# GS_02_Core.net
KiCad netlist of a schematic drawn in Altium Designer
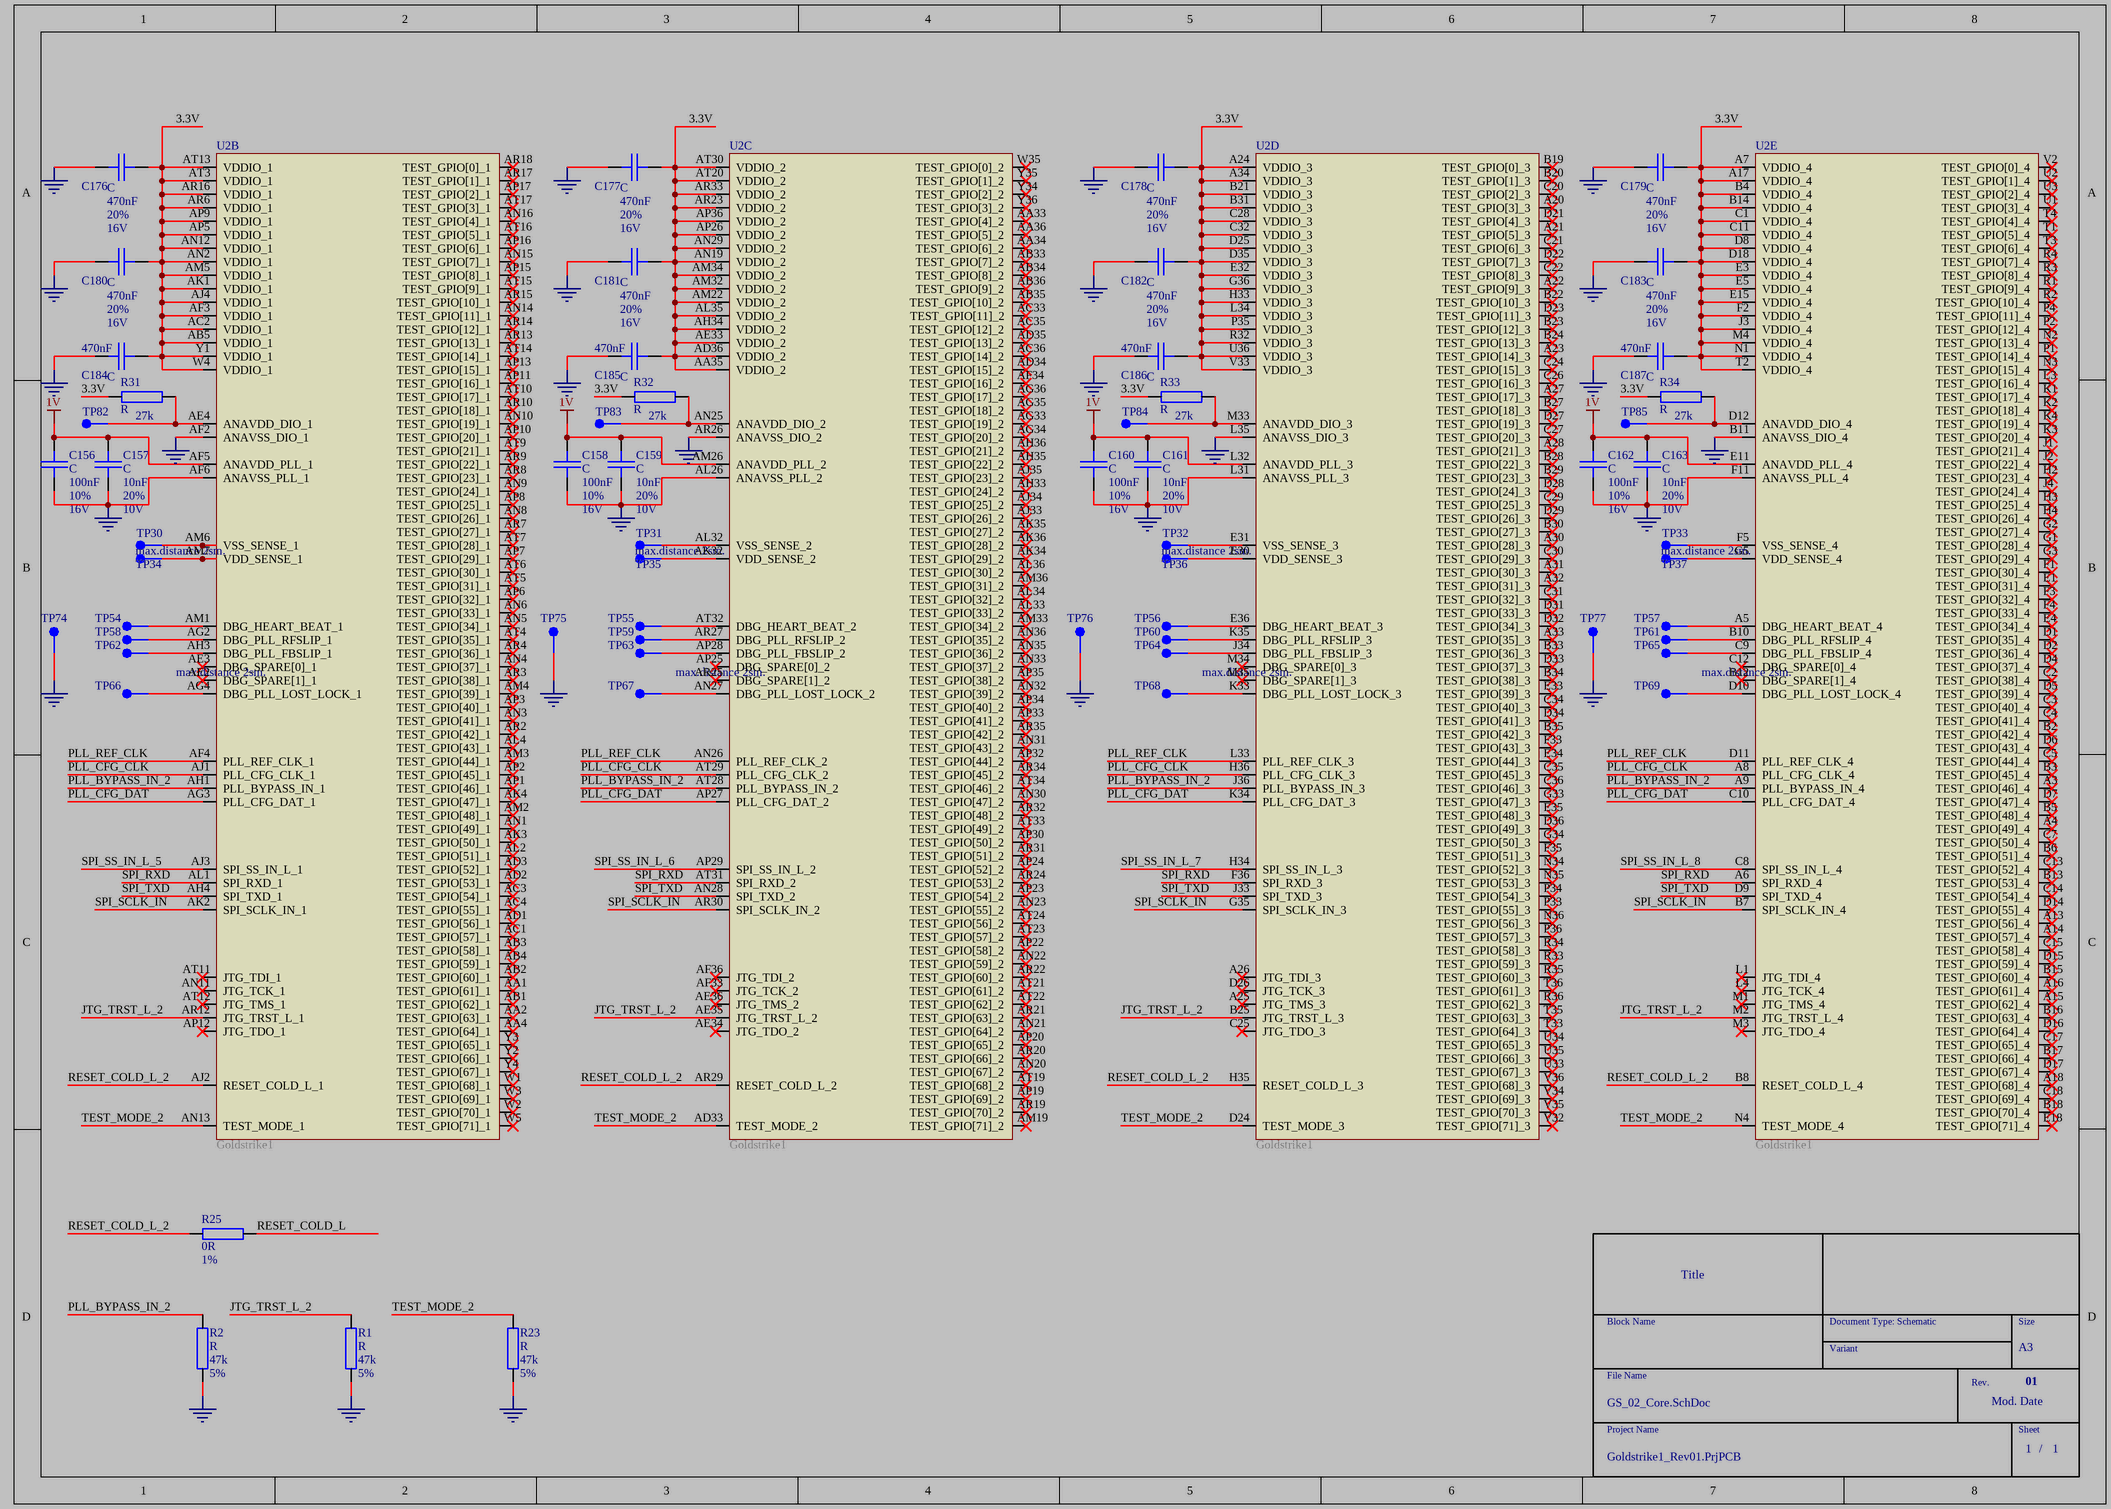
[diagram p0: GS_02_Core.SchDoc]

(export (version "E")
  (design (tool "Eeschema 10.0.6"))
  (components
    (comp (ref "C156")
      (value "C")
      (footprint "SMD_0603_CAPC1608X95N")
      (fields
        (field (name "DB_PART_NUMBER") "CAP000047357")
        (field (name "DB_VALUE") "100nF")
        (field (name "DB_TOLERANCE") "10%")
        (field (name "DB_VOLTAGE") "16V")
      )
      (libsource (lib "Database_Libs1") (part "C"))
    )
    (comp (ref "C157")
      (value "C")
      (footprint "SMD_0603_CAPC1608X95N")
      (fields
        (field (name "DB_PART_NUMBER") "CAP000038821")
        (field (name "DB_VALUE") "10nF")
        (field (name "DB_TOLERANCE") "20%")
        (field (name "DB_VOLTAGE") "10V")
      )
      (libsource (lib "Database_Libs1") (part "C"))
    )
    (comp (ref "C158")
      (value "C")
      (footprint "SMD_0603_CAPC1608X95N")
      (fields
        (field (name "DB_PART_NUMBER") "CAP000047357")
        (field (name "DB_VALUE") "100nF")
        (field (name "DB_TOLERANCE") "10%")
        (field (name "DB_VOLTAGE") "16V")
      )
      (libsource (lib "Database_Libs1") (part "C"))
    )
    (comp (ref "C159")
      (value "C")
      (footprint "SMD_0603_CAPC1608X95N")
      (fields
        (field (name "DB_PART_NUMBER") "CAP000038821")
        (field (name "DB_VALUE") "10nF")
        (field (name "DB_TOLERANCE") "20%")
        (field (name "DB_VOLTAGE") "10V")
      )
      (libsource (lib "Database_Libs1") (part "C"))
    )
    (comp (ref "C160")
      (value "C")
      (footprint "SMD_0603_CAPC1608X95N")
      (fields
        (field (name "DB_PART_NUMBER") "CAP000047357")
        (field (name "DB_VALUE") "100nF")
        (field (name "DB_TOLERANCE") "10%")
        (field (name "DB_VOLTAGE") "16V")
      )
      (libsource (lib "Database_Libs1") (part "C"))
    )
    (comp (ref "C161")
      (value "C")
      (footprint "SMD_0603_CAPC1608X95N")
      (fields
        (field (name "DB_PART_NUMBER") "CAP000038821")
        (field (name "DB_VALUE") "10nF")
        (field (name "DB_TOLERANCE") "20%")
        (field (name "DB_VOLTAGE") "10V")
      )
      (libsource (lib "Database_Libs1") (part "C"))
    )
    (comp (ref "C162")
      (value "C")
      (footprint "SMD_0603_CAPC1608X95N")
      (fields
        (field (name "DB_PART_NUMBER") "CAP000047357")
        (field (name "DB_VALUE") "100nF")
        (field (name "DB_TOLERANCE") "10%")
        (field (name "DB_VOLTAGE") "16V")
      )
      (libsource (lib "Database_Libs1") (part "C"))
    )
    (comp (ref "C163")
      (value "C")
      (footprint "SMD_0603_CAPC1608X95N")
      (fields
        (field (name "DB_PART_NUMBER") "CAP000038821")
        (field (name "DB_VALUE") "10nF")
        (field (name "DB_TOLERANCE") "20%")
        (field (name "DB_VOLTAGE") "10V")
      )
      (libsource (lib "Database_Libs1") (part "C"))
    )
    (comp (ref "C176")
      (value "C")
      (footprint "SMD_0603_CAPC1608X95N")
      (fields
        (field (name "DB_PART_NUMBER") "CAP000023179")
        (field (name "DB_VALUE") "470nF")
        (field (name "DB_TOLERANCE") "20%")
        (field (name "DB_VOLTAGE") "16V")
        (field (name "DB_MANUFACTURER_PART") "KEMET    C0603F474M4RAC")
      )
      (libsource (lib "Database_Libs1") (part "C"))
    )
    (comp (ref "C177")
      (value "C")
      (footprint "SMD_0603_CAPC1608X95N")
      (fields
        (field (name "DB_PART_NUMBER") "CAP000023179")
        (field (name "DB_VALUE") "470nF")
        (field (name "DB_TOLERANCE") "20%")
        (field (name "DB_VOLTAGE") "16V")
        (field (name "DB_MANUFACTURER_PART") "KEMET    C0603F474M4RAC")
      )
      (libsource (lib "Database_Libs1") (part "C"))
    )
    (comp (ref "C178")
      (value "C")
      (footprint "SMD_0603_CAPC1608X95N")
      (fields
        (field (name "DB_PART_NUMBER") "CAP000023179")
        (field (name "DB_VALUE") "470nF")
        (field (name "DB_TOLERANCE") "20%")
        (field (name "DB_VOLTAGE") "16V")
        (field (name "DB_MANUFACTURER_PART") "KEMET    C0603F474M4RAC")
      )
      (libsource (lib "Database_Libs1") (part "C"))
    )
    (comp (ref "C179")
      (value "C")
      (footprint "SMD_0603_CAPC1608X95N")
      (fields
        (field (name "DB_PART_NUMBER") "CAP000023179")
        (field (name "DB_VALUE") "470nF")
        (field (name "DB_TOLERANCE") "20%")
        (field (name "DB_VOLTAGE") "16V")
        (field (name "DB_MANUFACTURER_PART") "KEMET    C0603F474M4RAC")
      )
      (libsource (lib "Database_Libs1") (part "C"))
    )
    (comp (ref "C180")
      (value "C")
      (footprint "SMD_0603_CAPC1608X95N")
      (fields
        (field (name "DB_PART_NUMBER") "CAP000023179")
        (field (name "DB_VALUE") "470nF")
        (field (name "DB_TOLERANCE") "20%")
        (field (name "DB_VOLTAGE") "16V")
        (field (name "DB_MANUFACTURER_PART") "KEMET    C0603F474M4RAC")
      )
      (libsource (lib "Database_Libs1") (part "C"))
    )
    (comp (ref "C181")
      (value "C")
      (footprint "SMD_0603_CAPC1608X95N")
      (fields
        (field (name "DB_PART_NUMBER") "CAP000023179")
        (field (name "DB_VALUE") "470nF")
        (field (name "DB_TOLERANCE") "20%")
        (field (name "DB_VOLTAGE") "16V")
        (field (name "DB_MANUFACTURER_PART") "KEMET    C0603F474M4RAC")
      )
      (libsource (lib "Database_Libs1") (part "C"))
    )
    (comp (ref "C182")
      (value "C")
      (footprint "SMD_0603_CAPC1608X95N")
      (fields
        (field (name "DB_PART_NUMBER") "CAP000023179")
        (field (name "DB_VALUE") "470nF")
        (field (name "DB_TOLERANCE") "20%")
        (field (name "DB_VOLTAGE") "16V")
        (field (name "DB_MANUFACTURER_PART") "KEMET    C0603F474M4RAC")
      )
      (libsource (lib "Database_Libs1") (part "C"))
    )
    (comp (ref "C183")
      (value "C")
      (footprint "SMD_0603_CAPC1608X95N")
      (fields
        (field (name "DB_PART_NUMBER") "CAP000023179")
        (field (name "DB_VALUE") "470nF")
        (field (name "DB_TOLERANCE") "20%")
        (field (name "DB_VOLTAGE") "16V")
        (field (name "DB_MANUFACTURER_PART") "KEMET    C0603F474M4RAC")
      )
      (libsource (lib "Database_Libs1") (part "C"))
    )
    (comp (ref "C184")
      (value "C")
      (footprint "SMD_0603_CAPC1608X95N")
      (fields
        (field (name "DB_PART_NUMBER") "CAP000023179")
        (field (name "DB_VALUE") "470nF")
        (field (name "DB_MANUFACTURER_PART") "KEMET    C0603F474M4RAC")
      )
      (libsource (lib "Database_Libs1") (part "C"))
    )
    (comp (ref "C185")
      (value "C")
      (footprint "SMD_0603_CAPC1608X95N")
      (fields
        (field (name "DB_PART_NUMBER") "CAP000023179")
        (field (name "DB_VALUE") "470nF")
        (field (name "DB_MANUFACTURER_PART") "KEMET    C0603F474M4RAC")
      )
      (libsource (lib "Database_Libs1") (part "C"))
    )
    (comp (ref "C186")
      (value "C")
      (footprint "SMD_0603_CAPC1608X95N")
      (fields
        (field (name "DB_PART_NUMBER") "CAP000023179")
        (field (name "DB_VALUE") "470nF")
        (field (name "DB_MANUFACTURER_PART") "KEMET    C0603F474M4RAC")
      )
      (libsource (lib "Database_Libs1") (part "C"))
    )
    (comp (ref "C187")
      (value "C")
      (footprint "SMD_0603_CAPC1608X95N")
      (fields
        (field (name "DB_PART_NUMBER") "CAP000023179")
        (field (name "DB_VALUE") "470nF")
        (field (name "DB_MANUFACTURER_PART") "KEMET    C0603F474M4RAC")
      )
      (libsource (lib "Database_Libs1") (part "C"))
    )
    (comp (ref "R1")
      (value "R")
      (footprint "SMD_0603_RESC1608X55N")
      (fields
        (field (name "DB_PART_NUMBER") "RES000006462")
        (field (name "DB_VALUE") "47k")
        (field (name "DB_TOLERANCE") "5%")
        (field (name "DB_MANUFACTURER_PART") "YAGEO    RC0603JR-0747K")
      )
      (libsource (lib "Database_Libs1") (part "R"))
    )
    (comp (ref "R2")
      (value "R")
      (footprint "SMD_0603_RESC1608X55N")
      (fields
        (field (name "DB_PART_NUMBER") "RES000006462")
        (field (name "DB_VALUE") "47k")
        (field (name "DB_TOLERANCE") "5%")
        (field (name "DB_MANUFACTURER_PART") "YAGEO    RC0603JR-0747K")
      )
      (libsource (lib "Database_Libs1") (part "R"))
    )
    (comp (ref "R23")
      (value "R")
      (footprint "SMD_0603_RESC1608X55N")
      (fields
        (field (name "DB_PART_NUMBER") "RES000006462")
        (field (name "DB_VALUE") "47k")
        (field (name "DB_TOLERANCE") "5%")
        (field (name "DB_MANUFACTURER_PART") "YAGEO    RC0603JR-0747K")
      )
      (libsource (lib "Database_Libs1") (part "R"))
    )
    (comp (ref "R25")
      (value "R")
      (footprint "SMD_0603_RESC1608X55N")
      (fields
        (field (name "DB_PART_NUMBER") "RES000008926")
        (field (name "DB_VALUE") "0R")
        (field (name "DB_TOLERANCE") "1%")
        (field (name "DB_MANUFACTURER_PART") "YAGEO    AC0603FR-070RL")
        (field (name "DB_APPROVED_BY") "VSN")
      )
      (libsource (lib "Database_Libs1") (part "R"))
    )
    (comp (ref "R31")
      (value "R")
      (footprint "SMD_0603_RESC1608X55N")
      (fields
        (field (name "DB_PART_NUMBER") "RES000006456")
        (field (name "DB_VALUE") "27k")
        (field (name "DB_MANUFACTURER_PART") "YAGEO    RC0603JR-0727K")
      )
      (libsource (lib "Database_Libs1") (part "R"))
    )
    (comp (ref "R32")
      (value "R")
      (footprint "SMD_0603_RESC1608X55N")
      (fields
        (field (name "DB_PART_NUMBER") "RES000006456")
        (field (name "DB_VALUE") "27k")
        (field (name "DB_MANUFACTURER_PART") "YAGEO    RC0603JR-0727K")
      )
      (libsource (lib "Database_Libs1") (part "R"))
    )
    (comp (ref "R33")
      (value "R")
      (footprint "SMD_0603_RESC1608X55N")
      (fields
        (field (name "DB_PART_NUMBER") "RES000006456")
        (field (name "DB_VALUE") "27k")
        (field (name "DB_MANUFACTURER_PART") "YAGEO    RC0603JR-0727K")
      )
      (libsource (lib "Database_Libs1") (part "R"))
    )
    (comp (ref "R34")
      (value "R")
      (footprint "SMD_0603_RESC1608X55N")
      (fields
        (field (name "DB_PART_NUMBER") "RES000006456")
        (field (name "DB_VALUE") "27k")
        (field (name "DB_MANUFACTURER_PART") "YAGEO    RC0603JR-0727K")
      )
      (libsource (lib "Database_Libs1") (part "R"))
    )
    (comp (ref "TP30")
      (value "TEST_POINT_1")
      (footprint "SMD_TP_100-254")
      (fields (field (name "DB_PART_NUMBER") "TPO000000001"))
      (libsource (lib "Database_Libs1") (part "TEST_POINT_1"))
    )
    (comp (ref "TP31")
      (value "TEST_POINT_1")
      (footprint "SMD_TP_100-254")
      (fields (field (name "DB_PART_NUMBER") "TPO000000001"))
      (libsource (lib "Database_Libs1") (part "TEST_POINT_1"))
    )
    (comp (ref "TP32")
      (value "TEST_POINT_1")
      (footprint "SMD_TP_100-254")
      (fields (field (name "DB_PART_NUMBER") "TPO000000001"))
      (libsource (lib "Database_Libs1") (part "TEST_POINT_1"))
    )
    (comp (ref "TP33")
      (value "TEST_POINT_1")
      (footprint "SMD_TP_100-254")
      (fields (field (name "DB_PART_NUMBER") "TPO000000001"))
      (libsource (lib "Database_Libs1") (part "TEST_POINT_1"))
    )
    (comp (ref "TP34")
      (value "TEST_POINT_1")
      (footprint "SMD_TP_100-254")
      (fields (field (name "DB_PART_NUMBER") "TPO000000001"))
      (libsource (lib "Database_Libs1") (part "TEST_POINT_1"))
    )
    (comp (ref "TP35")
      (value "TEST_POINT_1")
      (footprint "SMD_TP_100-254")
      (fields (field (name "DB_PART_NUMBER") "TPO000000001"))
      (libsource (lib "Database_Libs1") (part "TEST_POINT_1"))
    )
    (comp (ref "TP36")
      (value "TEST_POINT_1")
      (footprint "SMD_TP_100-254")
      (fields (field (name "DB_PART_NUMBER") "TPO000000001"))
      (libsource (lib "Database_Libs1") (part "TEST_POINT_1"))
    )
    (comp (ref "TP37")
      (value "TEST_POINT_1")
      (footprint "SMD_TP_100-254")
      (fields (field (name "DB_PART_NUMBER") "TPO000000001"))
      (libsource (lib "Database_Libs1") (part "TEST_POINT_1"))
    )
    (comp (ref "TP54")
      (value "TEST_POINT_1")
      (footprint "SMD_TP_100-254")
      (fields (field (name "DB_PART_NUMBER") "TPO000000001"))
      (libsource (lib "Database_Libs1") (part "TEST_POINT_1"))
    )
    (comp (ref "TP55")
      (value "TEST_POINT_1")
      (footprint "SMD_TP_100-254")
      (fields (field (name "DB_PART_NUMBER") "TPO000000001"))
      (libsource (lib "Database_Libs1") (part "TEST_POINT_1"))
    )
    (comp (ref "TP56")
      (value "TEST_POINT_1")
      (footprint "SMD_TP_100-254")
      (fields (field (name "DB_PART_NUMBER") "TPO000000001"))
      (libsource (lib "Database_Libs1") (part "TEST_POINT_1"))
    )
    (comp (ref "TP57")
      (value "TEST_POINT_1")
      (footprint "SMD_TP_100-254")
      (fields (field (name "DB_PART_NUMBER") "TPO000000001"))
      (libsource (lib "Database_Libs1") (part "TEST_POINT_1"))
    )
    (comp (ref "TP58")
      (value "TEST_POINT_1")
      (footprint "SMD_TP_100-254")
      (fields (field (name "DB_PART_NUMBER") "TPO000000001"))
      (libsource (lib "Database_Libs1") (part "TEST_POINT_1"))
    )
    (comp (ref "TP59")
      (value "TEST_POINT_1")
      (footprint "SMD_TP_100-254")
      (fields (field (name "DB_PART_NUMBER") "TPO000000001"))
      (libsource (lib "Database_Libs1") (part "TEST_POINT_1"))
    )
    (comp (ref "TP60")
      (value "TEST_POINT_1")
      (footprint "SMD_TP_100-254")
      (fields (field (name "DB_PART_NUMBER") "TPO000000001"))
      (libsource (lib "Database_Libs1") (part "TEST_POINT_1"))
    )
    (comp (ref "TP61")
      (value "TEST_POINT_1")
      (footprint "SMD_TP_100-254")
      (fields (field (name "DB_PART_NUMBER") "TPO000000001"))
      (libsource (lib "Database_Libs1") (part "TEST_POINT_1"))
    )
    (comp (ref "TP62")
      (value "TEST_POINT_1")
      (footprint "SMD_TP_100-254")
      (fields (field (name "DB_PART_NUMBER") "TPO000000001"))
      (libsource (lib "Database_Libs1") (part "TEST_POINT_1"))
    )
    (comp (ref "TP63")
      (value "TEST_POINT_1")
      (footprint "SMD_TP_100-254")
      (fields (field (name "DB_PART_NUMBER") "TPO000000001"))
      (libsource (lib "Database_Libs1") (part "TEST_POINT_1"))
    )
    (comp (ref "TP64")
      (value "TEST_POINT_1")
      (footprint "SMD_TP_100-254")
      (fields (field (name "DB_PART_NUMBER") "TPO000000001"))
      (libsource (lib "Database_Libs1") (part "TEST_POINT_1"))
    )
    (comp (ref "TP65")
      (value "TEST_POINT_1")
      (footprint "SMD_TP_100-254")
      (fields (field (name "DB_PART_NUMBER") "TPO000000001"))
      (libsource (lib "Database_Libs1") (part "TEST_POINT_1"))
    )
    (comp (ref "TP66")
      (value "TEST_POINT_1")
      (footprint "SMD_TP_100-254")
      (fields (field (name "DB_PART_NUMBER") "TPO000000001"))
      (libsource (lib "Database_Libs1") (part "TEST_POINT_1"))
    )
    (comp (ref "TP67")
      (value "TEST_POINT_1")
      (footprint "SMD_TP_100-254")
      (fields (field (name "DB_PART_NUMBER") "TPO000000001"))
      (libsource (lib "Database_Libs1") (part "TEST_POINT_1"))
    )
    (comp (ref "TP68")
      (value "TEST_POINT_1")
      (footprint "SMD_TP_100-254")
      (fields (field (name "DB_PART_NUMBER") "TPO000000001"))
      (libsource (lib "Database_Libs1") (part "TEST_POINT_1"))
    )
    (comp (ref "TP69")
      (value "TEST_POINT_1")
      (footprint "SMD_TP_100-254")
      (fields (field (name "DB_PART_NUMBER") "TPO000000001"))
      (libsource (lib "Database_Libs1") (part "TEST_POINT_1"))
    )
    (comp (ref "TP74")
      (value "TEST_POINT_1")
      (footprint "SMD_TP_100-254")
      (fields (field (name "DB_PART_NUMBER") "TPO000000001"))
      (libsource (lib "Database_Libs1") (part "TEST_POINT_1"))
    )
    (comp (ref "TP75")
      (value "TEST_POINT_1")
      (footprint "SMD_TP_100-254")
      (fields (field (name "DB_PART_NUMBER") "TPO000000001"))
      (libsource (lib "Database_Libs1") (part "TEST_POINT_1"))
    )
    (comp (ref "TP76")
      (value "TEST_POINT_1")
      (footprint "SMD_TP_100-254")
      (fields (field (name "DB_PART_NUMBER") "TPO000000001"))
      (libsource (lib "Database_Libs1") (part "TEST_POINT_1"))
    )
    (comp (ref "TP77")
      (value "TEST_POINT_1")
      (footprint "SMD_TP_100-254")
      (fields (field (name "DB_PART_NUMBER") "TPO000000001"))
      (libsource (lib "Database_Libs1") (part "TEST_POINT_1"))
    )
    (comp (ref "TP82")
      (value "TEST_POINT_1")
      (footprint "SMD_TP_100-254")
      (fields (field (name "DB_PART_NUMBER") "TPO000000001"))
      (libsource (lib "Database_Libs1") (part "TEST_POINT_1"))
    )
    (comp (ref "TP83")
      (value "TEST_POINT_1")
      (footprint "SMD_TP_100-254")
      (fields (field (name "DB_PART_NUMBER") "TPO000000001"))
      (libsource (lib "Database_Libs1") (part "TEST_POINT_1"))
    )
    (comp (ref "TP84")
      (value "TEST_POINT_1")
      (footprint "SMD_TP_100-254")
      (fields (field (name "DB_PART_NUMBER") "TPO000000001"))
      (libsource (lib "Database_Libs1") (part "TEST_POINT_1"))
    )
    (comp (ref "TP85")
      (value "TEST_POINT_1")
      (footprint "SMD_TP_100-254")
      (fields (field (name "DB_PART_NUMBER") "TPO000000001"))
      (libsource (lib "Database_Libs1") (part "TEST_POINT_1"))
    )
    (comp (ref "U2") (value "Goldstrike1") (libsource (lib "Schlib1") (part "Goldstrike1")))
  )
  (nets
    (net (code "1") (name "/3.3V") (class "Default")
      (node (ref "C176") (pin "2") (pinfunction "2_2") (pintype "passive"))
      (node (ref "C177") (pin "2") (pinfunction "2_2") (pintype "passive"))
      (node (ref "C178") (pin "2") (pinfunction "2_2") (pintype "passive"))
      (node (ref "C179") (pin "2") (pinfunction "2_2") (pintype "passive"))
      (node (ref "C180") (pin "2") (pinfunction "2_2") (pintype "passive"))
      (node (ref "C181") (pin "2") (pinfunction "2_2") (pintype "passive"))
      (node (ref "C182") (pin "2") (pinfunction "2_2") (pintype "passive"))
      (node (ref "C183") (pin "2") (pinfunction "2_2") (pintype "passive"))
      (node (ref "C184") (pin "2") (pinfunction "2_2") (pintype "passive"))
      (node (ref "C185") (pin "2") (pinfunction "2_2") (pintype "passive"))
      (node (ref "C186") (pin "2") (pinfunction "2_2") (pintype "passive"))
      (node (ref "C187") (pin "2") (pinfunction "2_2") (pintype "passive"))
      (node (ref "R31") (pin "1") (pinfunction "1_1") (pintype "passive"))
      (node (ref "R32") (pin "1") (pinfunction "1_1") (pintype "passive"))
      (node (ref "R33") (pin "1") (pinfunction "1_1") (pintype "passive"))
      (node (ref "R34") (pin "1") (pinfunction "1_1") (pintype "passive"))
      (node (ref "U2") (pin "A17") (pinfunction "VDDIO_4_A17") (pintype "passive"))
      (node (ref "U2") (pin "A24") (pinfunction "VDDIO_3_A24") (pintype "passive"))
      (node (ref "U2") (pin "A34") (pinfunction "VDDIO_3_A34") (pintype "passive"))
      (node (ref "U2") (pin "A7") (pinfunction "VDDIO_4_A7") (pintype "passive"))
      (node (ref "U2") (pin "AA35") (pinfunction "VDDIO_2_AA35") (pintype "passive"))
      (node (ref "U2") (pin "AB5") (pinfunction "VDDIO_1_AB5") (pintype "passive"))
      (node (ref "U2") (pin "AC2") (pinfunction "VDDIO_1_AC2") (pintype "passive"))
      (node (ref "U2") (pin "AD36") (pinfunction "VDDIO_2_AD36") (pintype "passive"))
      (node (ref "U2") (pin "AE33") (pinfunction "VDDIO_2_AE33") (pintype "passive"))
      (node (ref "U2") (pin "AF3") (pinfunction "VDDIO_1_AF3") (pintype "passive"))
      (node (ref "U2") (pin "AH34") (pinfunction "VDDIO_2_AH34") (pintype "passive"))
      (node (ref "U2") (pin "AJ4") (pinfunction "VDDIO_1_AJ4") (pintype "passive"))
      (node (ref "U2") (pin "AK1") (pinfunction "VDDIO_1_AK1") (pintype "passive"))
      (node (ref "U2") (pin "AL35") (pinfunction "VDDIO_2_AL35") (pintype "passive"))
      (node (ref "U2") (pin "AM22") (pinfunction "VDDIO_2_AM22") (pintype "passive"))
      (node (ref "U2") (pin "AM32") (pinfunction "VDDIO_2_AM32") (pintype "passive"))
      (node (ref "U2") (pin "AM34") (pinfunction "VDDIO_2_AM34") (pintype "passive"))
      (node (ref "U2") (pin "AM5") (pinfunction "VDDIO_1_AM5") (pintype "passive"))
      (node (ref "U2") (pin "AN12") (pinfunction "VDDIO_1_AN12") (pintype "passive"))
      (node (ref "U2") (pin "AN19") (pinfunction "VDDIO_2_AN19") (pintype "passive"))
      (node (ref "U2") (pin "AN2") (pinfunction "VDDIO_1_AN2") (pintype "passive"))
      (node (ref "U2") (pin "AN29") (pinfunction "VDDIO_2_AN29") (pintype "passive"))
      (node (ref "U2") (pin "AP26") (pinfunction "VDDIO_2_AP26") (pintype "passive"))
      (node (ref "U2") (pin "AP36") (pinfunction "VDDIO_2_AP36") (pintype "passive"))
      (node (ref "U2") (pin "AP5") (pinfunction "VDDIO_1_AP5") (pintype "passive"))
      (node (ref "U2") (pin "AP9") (pinfunction "VDDIO_1_AP9") (pintype "passive"))
      (node (ref "U2") (pin "AR16") (pinfunction "VDDIO_1_AR16") (pintype "passive"))
      (node (ref "U2") (pin "AR23") (pinfunction "VDDIO_2_AR23") (pintype "passive"))
      (node (ref "U2") (pin "AR33") (pinfunction "VDDIO_2_AR33") (pintype "passive"))
      (node (ref "U2") (pin "AR6") (pinfunction "VDDIO_1_AR6") (pintype "passive"))
      (node (ref "U2") (pin "AT13") (pinfunction "VDDIO_1_AT13") (pintype "passive"))
      (node (ref "U2") (pin "AT20") (pinfunction "VDDIO_2_AT20") (pintype "passive"))
      (node (ref "U2") (pin "AT3") (pinfunction "VDDIO_1_AT3") (pintype "passive"))
      (node (ref "U2") (pin "AT30") (pinfunction "VDDIO_2_AT30") (pintype "passive"))
      (node (ref "U2") (pin "B14") (pinfunction "VDDIO_4_B14") (pintype "passive"))
      (node (ref "U2") (pin "B21") (pinfunction "VDDIO_3_B21") (pintype "passive"))
      (node (ref "U2") (pin "B31") (pinfunction "VDDIO_3_B31") (pintype "passive"))
      (node (ref "U2") (pin "B4") (pinfunction "VDDIO_4_B4") (pintype "passive"))
      (node (ref "U2") (pin "C1") (pinfunction "VDDIO_4_C1") (pintype "passive"))
      (node (ref "U2") (pin "C11") (pinfunction "VDDIO_4_C11") (pintype "passive"))
      (node (ref "U2") (pin "C28") (pinfunction "VDDIO_3_C28") (pintype "passive"))
      (node (ref "U2") (pin "C32") (pinfunction "VDDIO_3_C32") (pintype "passive"))
      (node (ref "U2") (pin "D18") (pinfunction "VDDIO_4_D18") (pintype "passive"))
      (node (ref "U2") (pin "D25") (pinfunction "VDDIO_3_D25") (pintype "passive"))
      (node (ref "U2") (pin "D35") (pinfunction "VDDIO_3_D35") (pintype "passive"))
      (node (ref "U2") (pin "D8") (pinfunction "VDDIO_4_D8") (pintype "passive"))
      (node (ref "U2") (pin "E15") (pinfunction "VDDIO_4_E15") (pintype "passive"))
      (node (ref "U2") (pin "E3") (pinfunction "VDDIO_4_E3") (pintype "passive"))
      (node (ref "U2") (pin "E32") (pinfunction "VDDIO_3_E32") (pintype "passive"))
      (node (ref "U2") (pin "E5") (pinfunction "VDDIO_4_E5") (pintype "passive"))
      (node (ref "U2") (pin "F2") (pinfunction "VDDIO_4_F2") (pintype "passive"))
      (node (ref "U2") (pin "G36") (pinfunction "VDDIO_3_G36") (pintype "passive"))
      (node (ref "U2") (pin "H33") (pinfunction "VDDIO_3_H33") (pintype "passive"))
      (node (ref "U2") (pin "J3") (pinfunction "VDDIO_4_J3") (pintype "passive"))
      (node (ref "U2") (pin "L34") (pinfunction "VDDIO_3_L34") (pintype "passive"))
      (node (ref "U2") (pin "M4") (pinfunction "VDDIO_4_M4") (pintype "passive"))
      (node (ref "U2") (pin "N1") (pinfunction "VDDIO_4_N1") (pintype "passive"))
      (node (ref "U2") (pin "P35") (pinfunction "VDDIO_3_P35") (pintype "passive"))
      (node (ref "U2") (pin "R32") (pinfunction "VDDIO_3_R32") (pintype "passive"))
      (node (ref "U2") (pin "T2") (pinfunction "VDDIO_4_T2") (pintype "passive"))
      (node (ref "U2") (pin "U36") (pinfunction "VDDIO_3_U36") (pintype "passive"))
      (node (ref "U2") (pin "V33") (pinfunction "VDDIO_3_V33") (pintype "passive"))
      (node (ref "U2") (pin "W4") (pinfunction "VDDIO_1_W4") (pintype "passive"))
      (node (ref "U2") (pin "Y1") (pinfunction "VDDIO_1_Y1") (pintype "passive"))
    )
    (net (code "2") (name "/JTG_TRST_L_2") (class "Default")
      (node (ref "R1") (pin "1") (pinfunction "1_1") (pintype "passive"))
      (node (ref "U2") (pin "AE35") (pinfunction "JTG_TRST_L_2_AE35") (pintype "passive"))
      (node (ref "U2") (pin "AR12") (pinfunction "JTG_TRST_L_1_AR12") (pintype "passive"))
      (node (ref "U2") (pin "B25") (pinfunction "JTG_TRST_L_3_B25") (pintype "passive"))
      (node (ref "U2") (pin "M2") (pinfunction "JTG_TRST_L_4_M2") (pintype "passive"))
    )
    (net (code "3") (name "/PLL_BYPASS_IN_2") (class "Default")
      (node (ref "R2") (pin "1") (pinfunction "1_1") (pintype "passive"))
      (node (ref "U2") (pin "A9") (pinfunction "PLL_BYPASS_IN_4_A9") (pintype "passive"))
      (node (ref "U2") (pin "AH1") (pinfunction "PLL_BYPASS_IN_1_AH1") (pintype "passive"))
      (node (ref "U2") (pin "AT28") (pinfunction "PLL_BYPASS_IN_2_AT28") (pintype "passive"))
      (node (ref "U2") (pin "J36") (pinfunction "PLL_BYPASS_IN_3_J36") (pintype "passive"))
    )
    (net (code "4") (name "/PLL_CFG_CLK") (class "Default")
      (node (ref "U2") (pin "A8") (pinfunction "PLL_CFG_CLK_4_A8") (pintype "passive"))
      (node (ref "U2") (pin "AJ1") (pinfunction "PLL_CFG_CLK_1_AJ1") (pintype "passive"))
      (node (ref "U2") (pin "AT29") (pinfunction "PLL_CFG_CLK_2_AT29") (pintype "passive"))
      (node (ref "U2") (pin "H36") (pinfunction "PLL_CFG_CLK_3_H36") (pintype "passive"))
    )
    (net (code "5") (name "/PLL_CFG_DAT") (class "Default")
      (node (ref "U2") (pin "AG3") (pinfunction "PLL_CFG_DAT_1_AG3") (pintype "passive"))
      (node (ref "U2") (pin "AP27") (pinfunction "PLL_CFG_DAT_2_AP27") (pintype "passive"))
      (node (ref "U2") (pin "C10") (pinfunction "PLL_CFG_DAT_4_C10") (pintype "passive"))
      (node (ref "U2") (pin "K34") (pinfunction "PLL_CFG_DAT_3_K34") (pintype "passive"))
    )
    (net (code "6") (name "/PLL_REF_CLK") (class "Default")
      (node (ref "U2") (pin "AF4") (pinfunction "PLL_REF_CLK_1_AF4") (pintype "passive"))
      (node (ref "U2") (pin "AN26") (pinfunction "PLL_REF_CLK_2_AN26") (pintype "passive"))
      (node (ref "U2") (pin "D11") (pinfunction "PLL_REF_CLK_4_D11") (pintype "passive"))
      (node (ref "U2") (pin "L33") (pinfunction "PLL_REF_CLK_3_L33") (pintype "passive"))
    )
    (net (code "7") (name "/RESET_COLD_L") (class "Default")
      (node (ref "R25") (pin "1") (pinfunction "1_1") (pintype "passive"))
    )
    (net (code "8") (name "/RESET_COLD_L_2") (class "Default")
      (node (ref "R25") (pin "2") (pinfunction "2_2") (pintype "passive"))
      (node (ref "U2") (pin "AJ2") (pinfunction "RESET_COLD_L_1_AJ2") (pintype "passive"))
      (node (ref "U2") (pin "AR29") (pinfunction "RESET_COLD_L_2_AR29") (pintype "passive"))
      (node (ref "U2") (pin "B8") (pinfunction "RESET_COLD_L_4_B8") (pintype "passive"))
      (node (ref "U2") (pin "H35") (pinfunction "RESET_COLD_L_3_H35") (pintype "passive"))
    )
    (net (code "9") (name "/SPI_RXD") (class "Default")
      (node (ref "U2") (pin "A6") (pinfunction "SPI_RXD_4_A6") (pintype "passive"))
      (node (ref "U2") (pin "AL1") (pinfunction "SPI_RXD_1_AL1") (pintype "passive"))
      (node (ref "U2") (pin "AT31") (pinfunction "SPI_RXD_2_AT31") (pintype "passive"))
      (node (ref "U2") (pin "F36") (pinfunction "SPI_RXD_3_F36") (pintype "passive"))
    )
    (net (code "10") (name "/SPI_SCLK_IN") (class "Default")
      (node (ref "U2") (pin "AK2") (pinfunction "SPI_SCLK_IN_1_AK2") (pintype "passive"))
      (node (ref "U2") (pin "AR30") (pinfunction "SPI_SCLK_IN_2_AR30") (pintype "passive"))
      (node (ref "U2") (pin "B7") (pinfunction "SPI_SCLK_IN_4_B7") (pintype "passive"))
      (node (ref "U2") (pin "G35") (pinfunction "SPI_SCLK_IN_3_G35") (pintype "passive"))
    )
    (net (code "11") (name "/SPI_SS_IN_L_5") (class "Default")
      (node (ref "U2") (pin "AJ3") (pinfunction "SPI_SS_IN_L_1_AJ3") (pintype "passive"))
    )
    (net (code "12") (name "/SPI_SS_IN_L_6") (class "Default")
      (node (ref "U2") (pin "AP29") (pinfunction "SPI_SS_IN_L_2_AP29") (pintype "passive"))
    )
    (net (code "13") (name "/SPI_SS_IN_L_7") (class "Default")
      (node (ref "U2") (pin "H34") (pinfunction "SPI_SS_IN_L_3_H34") (pintype "passive"))
    )
    (net (code "14") (name "/SPI_SS_IN_L_8") (class "Default")
      (node (ref "U2") (pin "C8") (pinfunction "SPI_SS_IN_L_4_C8") (pintype "passive"))
    )
    (net (code "15") (name "/SPI_TXD") (class "Default")
      (node (ref "U2") (pin "AH4") (pinfunction "SPI_TXD_1_AH4") (pintype "passive"))
      (node (ref "U2") (pin "AN28") (pinfunction "SPI_TXD_2_AN28") (pintype "passive"))
      (node (ref "U2") (pin "D9") (pinfunction "SPI_TXD_4_D9") (pintype "passive"))
      (node (ref "U2") (pin "J33") (pinfunction "SPI_TXD_3_J33") (pintype "passive"))
    )
    (net (code "16") (name "/TEST_MODE_2") (class "Default")
      (node (ref "R23") (pin "1") (pinfunction "1_1") (pintype "passive"))
      (node (ref "U2") (pin "AD33") (pinfunction "TEST_MODE_2_AD33") (pintype "passive"))
      (node (ref "U2") (pin "AN13") (pinfunction "TEST_MODE_1_AN13") (pintype "passive"))
      (node (ref "U2") (pin "D24") (pinfunction "TEST_MODE_3_D24") (pintype "passive"))
      (node (ref "U2") (pin "N4") (pinfunction "TEST_MODE_4_N4") (pintype "passive"))
    )
    (net (code "17") (name "1V") (class "Default")
      (node (ref "C156") (pin "1") (pinfunction "1_1") (pintype "passive"))
      (node (ref "C157") (pin "1") (pinfunction "1_1") (pintype "passive"))
      (node (ref "C158") (pin "1") (pinfunction "1_1") (pintype "passive"))
      (node (ref "C159") (pin "1") (pinfunction "1_1") (pintype "passive"))
      (node (ref "C160") (pin "1") (pinfunction "1_1") (pintype "passive"))
      (node (ref "C161") (pin "1") (pinfunction "1_1") (pintype "passive"))
      (node (ref "C162") (pin "1") (pinfunction "1_1") (pintype "passive"))
      (node (ref "C163") (pin "1") (pinfunction "1_1") (pintype "passive"))
      (node (ref "U2") (pin "AF5") (pinfunction "ANAVDD_PLL_1_AF5") (pintype "passive"))
      (node (ref "U2") (pin "AM26") (pinfunction "ANAVDD_PLL_2_AM26") (pintype "passive"))
      (node (ref "U2") (pin "E11") (pinfunction "ANAVDD_PLL_4_E11") (pintype "passive"))
      (node (ref "U2") (pin "L32") (pinfunction "ANAVDD_PLL_3_L32") (pintype "passive"))
    )
    (net (code "18") (name "GND") (class "Default")
      (node (ref "C156") (pin "2") (pinfunction "2_2") (pintype "passive"))
      (node (ref "C157") (pin "2") (pinfunction "2_2") (pintype "passive"))
      (node (ref "C158") (pin "2") (pinfunction "2_2") (pintype "passive"))
      (node (ref "C159") (pin "2") (pinfunction "2_2") (pintype "passive"))
      (node (ref "C160") (pin "2") (pinfunction "2_2") (pintype "passive"))
      (node (ref "C161") (pin "2") (pinfunction "2_2") (pintype "passive"))
      (node (ref "C162") (pin "2") (pinfunction "2_2") (pintype "passive"))
      (node (ref "C163") (pin "2") (pinfunction "2_2") (pintype "passive"))
      (node (ref "C176") (pin "1") (pinfunction "1_1") (pintype "passive"))
      (node (ref "C177") (pin "1") (pinfunction "1_1") (pintype "passive"))
      (node (ref "C178") (pin "1") (pinfunction "1_1") (pintype "passive"))
      (node (ref "C179") (pin "1") (pinfunction "1_1") (pintype "passive"))
      (node (ref "C180") (pin "1") (pinfunction "1_1") (pintype "passive"))
      (node (ref "C181") (pin "1") (pinfunction "1_1") (pintype "passive"))
      (node (ref "C182") (pin "1") (pinfunction "1_1") (pintype "passive"))
      (node (ref "C183") (pin "1") (pinfunction "1_1") (pintype "passive"))
      (node (ref "C184") (pin "1") (pinfunction "1_1") (pintype "passive"))
      (node (ref "C185") (pin "1") (pinfunction "1_1") (pintype "passive"))
      (node (ref "C186") (pin "1") (pinfunction "1_1") (pintype "passive"))
      (node (ref "C187") (pin "1") (pinfunction "1_1") (pintype "passive"))
      (node (ref "R1") (pin "2") (pinfunction "2_2") (pintype "passive"))
      (node (ref "R2") (pin "2") (pinfunction "2_2") (pintype "passive"))
      (node (ref "R23") (pin "2") (pinfunction "2_2") (pintype "passive"))
      (node (ref "TP74") (pin "1") (pinfunction "1_1") (pintype "passive"))
      (node (ref "TP75") (pin "1") (pinfunction "1_1") (pintype "passive"))
      (node (ref "TP76") (pin "1") (pinfunction "1_1") (pintype "passive"))
      (node (ref "TP77") (pin "1") (pinfunction "1_1") (pintype "passive"))
      (node (ref "U2") (pin "AF2") (pinfunction "ANAVSS_DIO_1_AF2") (pintype "passive"))
      (node (ref "U2") (pin "AF6") (pinfunction "ANAVSS_PLL_1_AF6") (pintype "passive"))
      (node (ref "U2") (pin "AL26") (pinfunction "ANAVSS_PLL_2_AL26") (pintype "passive"))
      (node (ref "U2") (pin "AR26") (pinfunction "ANAVSS_DIO_2_AR26") (pintype "passive"))
      (node (ref "U2") (pin "B11") (pinfunction "ANAVSS_DIO_4_B11") (pintype "passive"))
      (node (ref "U2") (pin "F11") (pinfunction "ANAVSS_PLL_4_F11") (pintype "passive"))
      (node (ref "U2") (pin "L31") (pinfunction "ANAVSS_PLL_3_L31") (pintype "passive"))
      (node (ref "U2") (pin "L35") (pinfunction "ANAVSS_DIO_3_L35") (pintype "passive"))
    )
    (net (code "19") (name "Net-(U2B-ANAVDD_DIO_1)") (class "Default")
      (node (ref "R31") (pin "2") (pinfunction "2_2") (pintype "passive"))
      (node (ref "TP82") (pin "1") (pinfunction "1_1") (pintype "passive"))
      (node (ref "U2") (pin "AE4") (pinfunction "ANAVDD_DIO_1_AE4") (pintype "passive"))
    )
    (net (code "20") (name "Net-(U2B-DBG_HEART_BEAT_1)") (class "Default")
      (node (ref "TP54") (pin "1") (pinfunction "1_1") (pintype "passive"))
      (node (ref "U2") (pin "AM1") (pinfunction "DBG_HEART_BEAT_1_AM1") (pintype "passive"))
    )
    (net (code "21") (name "Net-(U2B-DBG_PLL_FBSLIP_1)") (class "Default")
      (node (ref "TP62") (pin "1") (pinfunction "1_1") (pintype "passive"))
      (node (ref "U2") (pin "AH3") (pinfunction "DBG_PLL_FBSLIP_1_AH3") (pintype "passive"))
    )
    (net (code "22") (name "Net-(U2B-DBG_PLL_LOST_LOCK_1)") (class "Default")
      (node (ref "TP66") (pin "1") (pinfunction "1_1") (pintype "passive"))
      (node (ref "U2") (pin "AG4") (pinfunction "DBG_PLL_LOST_LOCK_1_AG4") (pintype "passive"))
    )
    (net (code "23") (name "Net-(U2B-DBG_PLL_RFSLIP_1)") (class "Default")
      (node (ref "TP58") (pin "1") (pinfunction "1_1") (pintype "passive"))
      (node (ref "U2") (pin "AG2") (pinfunction "DBG_PLL_RFSLIP_1_AG2") (pintype "passive"))
    )
    (net (code "24") (name "Net-(U2B-VDD_SENSE_1)") (class "Default")
      (node (ref "TP34") (pin "1") (pinfunction "1_1") (pintype "passive"))
      (node (ref "U2") (pin "AM7") (pinfunction "VDD_SENSE_1_AM7") (pintype "passive"))
    )
    (net (code "25") (name "Net-(U2B-VSS_SENSE_1)") (class "Default")
      (node (ref "TP30") (pin "1") (pinfunction "1_1") (pintype "passive"))
      (node (ref "U2") (pin "AM6") (pinfunction "VSS_SENSE_1_AM6") (pintype "passive"))
    )
    (net (code "26") (name "Net-(U2C-ANAVDD_DIO_2)") (class "Default")
      (node (ref "R32") (pin "2") (pinfunction "2_2") (pintype "passive"))
      (node (ref "TP83") (pin "1") (pinfunction "1_1") (pintype "passive"))
      (node (ref "U2") (pin "AN25") (pinfunction "ANAVDD_DIO_2_AN25") (pintype "passive"))
    )
    (net (code "27") (name "Net-(U2C-DBG_HEART_BEAT_2)") (class "Default")
      (node (ref "TP55") (pin "1") (pinfunction "1_1") (pintype "passive"))
      (node (ref "U2") (pin "AT32") (pinfunction "DBG_HEART_BEAT_2_AT32") (pintype "passive"))
    )
    (net (code "28") (name "Net-(U2C-DBG_PLL_FBSLIP_2)") (class "Default")
      (node (ref "TP63") (pin "1") (pinfunction "1_1") (pintype "passive"))
      (node (ref "U2") (pin "AP28") (pinfunction "DBG_PLL_FBSLIP_2_AP28") (pintype "passive"))
    )
    (net (code "29") (name "Net-(U2C-DBG_PLL_LOST_LOCK_2)") (class "Default")
      (node (ref "TP67") (pin "1") (pinfunction "1_1") (pintype "passive"))
      (node (ref "U2") (pin "AN27") (pinfunction "DBG_PLL_LOST_LOCK_2_AN27") (pintype "passive"))
    )
    (net (code "30") (name "Net-(U2C-DBG_PLL_RFSLIP_2)") (class "Default")
      (node (ref "TP59") (pin "1") (pinfunction "1_1") (pintype "passive"))
      (node (ref "U2") (pin "AR27") (pinfunction "DBG_PLL_RFSLIP_2_AR27") (pintype "passive"))
    )
    (net (code "31") (name "Net-(U2C-VDD_SENSE_2)") (class "Default")
      (node (ref "TP35") (pin "1") (pinfunction "1_1") (pintype "passive"))
      (node (ref "U2") (pin "AK32") (pinfunction "VDD_SENSE_2_AK32") (pintype "passive"))
    )
    (net (code "32") (name "Net-(U2C-VSS_SENSE_2)") (class "Default")
      (node (ref "TP31") (pin "1") (pinfunction "1_1") (pintype "passive"))
      (node (ref "U2") (pin "AL32") (pinfunction "VSS_SENSE_2_AL32") (pintype "passive"))
    )
    (net (code "33") (name "Net-(U2D-ANAVDD_DIO_3)") (class "Default")
      (node (ref "R33") (pin "2") (pinfunction "2_2") (pintype "passive"))
      (node (ref "TP84") (pin "1") (pinfunction "1_1") (pintype "passive"))
      (node (ref "U2") (pin "M33") (pinfunction "ANAVDD_DIO_3_M33") (pintype "passive"))
    )
    (net (code "34") (name "Net-(U2D-DBG_HEART_BEAT_3)") (class "Default")
      (node (ref "TP56") (pin "1") (pinfunction "1_1") (pintype "passive"))
      (node (ref "U2") (pin "E36") (pinfunction "DBG_HEART_BEAT_3_E36") (pintype "passive"))
    )
    (net (code "35") (name "Net-(U2D-DBG_PLL_FBSLIP_3)") (class "Default")
      (node (ref "TP64") (pin "1") (pinfunction "1_1") (pintype "passive"))
      (node (ref "U2") (pin "J34") (pinfunction "DBG_PLL_FBSLIP_3_J34") (pintype "passive"))
    )
    (net (code "36") (name "Net-(U2D-DBG_PLL_LOST_LOCK_3)") (class "Default")
      (node (ref "TP68") (pin "1") (pinfunction "1_1") (pintype "passive"))
      (node (ref "U2") (pin "K33") (pinfunction "DBG_PLL_LOST_LOCK_3_K33") (pintype "passive"))
    )
    (net (code "37") (name "Net-(U2D-DBG_PLL_RFSLIP_3)") (class "Default")
      (node (ref "TP60") (pin "1") (pinfunction "1_1") (pintype "passive"))
      (node (ref "U2") (pin "K35") (pinfunction "DBG_PLL_RFSLIP_3_K35") (pintype "passive"))
    )
    (net (code "38") (name "Net-(U2D-VDD_SENSE_3)") (class "Default")
      (node (ref "TP36") (pin "1") (pinfunction "1_1") (pintype "passive"))
      (node (ref "U2") (pin "E30") (pinfunction "VDD_SENSE_3_E30") (pintype "passive"))
    )
    (net (code "39") (name "Net-(U2D-VSS_SENSE_3)") (class "Default")
      (node (ref "TP32") (pin "1") (pinfunction "1_1") (pintype "passive"))
      (node (ref "U2") (pin "E31") (pinfunction "VSS_SENSE_3_E31") (pintype "passive"))
    )
    (net (code "40") (name "Net-(U2E-ANAVDD_DIO_4)") (class "Default")
      (node (ref "R34") (pin "2") (pinfunction "2_2") (pintype "passive"))
      (node (ref "TP85") (pin "1") (pinfunction "1_1") (pintype "passive"))
      (node (ref "U2") (pin "D12") (pinfunction "ANAVDD_DIO_4_D12") (pintype "passive"))
    )
    (net (code "41") (name "Net-(U2E-DBG_HEART_BEAT_4)") (class "Default")
      (node (ref "TP57") (pin "1") (pinfunction "1_1") (pintype "passive"))
      (node (ref "U2") (pin "A5") (pinfunction "DBG_HEART_BEAT_4_A5") (pintype "passive"))
    )
    (net (code "42") (name "Net-(U2E-DBG_PLL_FBSLIP_4)") (class "Default")
      (node (ref "TP65") (pin "1") (pinfunction "1_1") (pintype "passive"))
      (node (ref "U2") (pin "C9") (pinfunction "DBG_PLL_FBSLIP_4_C9") (pintype "passive"))
    )
    (net (code "43") (name "Net-(U2E-DBG_PLL_LOST_LOCK_4)") (class "Default")
      (node (ref "TP69") (pin "1") (pinfunction "1_1") (pintype "passive"))
      (node (ref "U2") (pin "D10") (pinfunction "DBG_PLL_LOST_LOCK_4_D10") (pintype "passive"))
    )
    (net (code "44") (name "Net-(U2E-DBG_PLL_RFSLIP_4)") (class "Default")
      (node (ref "TP61") (pin "1") (pinfunction "1_1") (pintype "passive"))
      (node (ref "U2") (pin "B10") (pinfunction "DBG_PLL_RFSLIP_4_B10") (pintype "passive"))
    )
    (net (code "45") (name "Net-(U2E-VDD_SENSE_4)") (class "Default")
      (node (ref "TP37") (pin "1") (pinfunction "1_1") (pintype "passive"))
      (node (ref "U2") (pin "G5") (pinfunction "VDD_SENSE_4_G5") (pintype "passive"))
    )
    (net (code "46") (name "Net-(U2E-VSS_SENSE_4)") (class "Default")
      (node (ref "TP33") (pin "1") (pinfunction "1_1") (pintype "passive"))
      (node (ref "U2") (pin "F5") (pinfunction "VSS_SENSE_4_F5") (pintype "passive"))
    )
    (net (code "47") (name "unconnected-(U2B-DBG_SPARE[0]_1-PadAE3)") (class "Default")
      (node (ref "U2") (pin "AE3") (pinfunction "DBG_SPARE[0]_1_AE3") (pintype "passive+no_connect"))
    )
    (net (code "48") (name "unconnected-(U2B-DBG_SPARE[1]_1-PadAE2)") (class "Default")
      (node (ref "U2") (pin "AE2") (pinfunction "DBG_SPARE[1]_1_AE2") (pintype "passive+no_connect"))
    )
    (net (code "49") (name "unconnected-(U2B-JTG_TCK_1-PadAN11)") (class "Default")
      (node (ref "U2") (pin "AN11") (pinfunction "JTG_TCK_1_AN11") (pintype "passive+no_connect"))
    )
    (net (code "50") (name "unconnected-(U2B-JTG_TDI_1-PadAT11)") (class "Default")
      (node (ref "U2") (pin "AT11") (pinfunction "JTG_TDI_1_AT11") (pintype "passive+no_connect"))
    )
    (net (code "51") (name "unconnected-(U2B-JTG_TDO_1-PadAP12)") (class "Default")
      (node (ref "U2") (pin "AP12") (pinfunction "JTG_TDO_1_AP12") (pintype "passive+no_connect"))
    )
    (net (code "52") (name "unconnected-(U2B-JTG_TMS_1-PadAT12)") (class "Default")
      (node (ref "U2") (pin "AT12") (pinfunction "JTG_TMS_1_AT12") (pintype "passive+no_connect"))
    )
    (net (code "53") (name "unconnected-(U2B-TEST_GPIO[0]_1-PadAR18)") (class "Default")
      (node (ref "U2") (pin "AR18") (pinfunction "TEST_GPIO[0]_1_AR18") (pintype "passive+no_connect"))
    )
    (net (code "54") (name "unconnected-(U2B-TEST_GPIO[1]_1-PadAR17)") (class "Default")
      (node (ref "U2") (pin "AR17") (pinfunction "TEST_GPIO[1]_1_AR17") (pintype "passive+no_connect"))
    )
    (net (code "55") (name "unconnected-(U2B-TEST_GPIO[2]_1-PadAP17)") (class "Default")
      (node (ref "U2") (pin "AP17") (pinfunction "TEST_GPIO[2]_1_AP17") (pintype "passive+no_connect"))
    )
    (net (code "56") (name "unconnected-(U2B-TEST_GPIO[3]_1-PadAT17)") (class "Default")
      (node (ref "U2") (pin "AT17") (pinfunction "TEST_GPIO[3]_1_AT17") (pintype "passive+no_connect"))
    )
    (net (code "57") (name "unconnected-(U2B-TEST_GPIO[4]_1-PadAN16)") (class "Default")
      (node (ref "U2") (pin "AN16") (pinfunction "TEST_GPIO[4]_1_AN16") (pintype "passive+no_connect"))
    )
    (net (code "58") (name "unconnected-(U2B-TEST_GPIO[5]_1-PadAT16)") (class "Default")
      (node (ref "U2") (pin "AT16") (pinfunction "TEST_GPIO[5]_1_AT16") (pintype "passive+no_connect"))
    )
    (net (code "59") (name "unconnected-(U2B-TEST_GPIO[6]_1-PadAP16)") (class "Default")
      (node (ref "U2") (pin "AP16") (pinfunction "TEST_GPIO[6]_1_AP16") (pintype "passive+no_connect"))
    )
    (net (code "60") (name "unconnected-(U2B-TEST_GPIO[7]_1-PadAN15)") (class "Default")
      (node (ref "U2") (pin "AN15") (pinfunction "TEST_GPIO[7]_1_AN15") (pintype "passive+no_connect"))
    )
    (net (code "61") (name "unconnected-(U2B-TEST_GPIO[8]_1-PadAP15)") (class "Default")
      (node (ref "U2") (pin "AP15") (pinfunction "TEST_GPIO[8]_1_AP15") (pintype "passive+no_connect"))
    )
    (net (code "62") (name "unconnected-(U2B-TEST_GPIO[9]_1-PadAT15)") (class "Default")
      (node (ref "U2") (pin "AT15") (pinfunction "TEST_GPIO[9]_1_AT15") (pintype "passive+no_connect"))
    )
    (net (code "63") (name "unconnected-(U2B-TEST_GPIO[10]_1-PadAR15)") (class "Default")
      (node (ref "U2") (pin "AR15") (pinfunction "TEST_GPIO[10]_1_AR15") (pintype "passive+no_connect"))
    )
    (net (code "64") (name "unconnected-(U2B-TEST_GPIO[11]_1-PadAN14)") (class "Default")
      (node (ref "U2") (pin "AN14") (pinfunction "TEST_GPIO[11]_1_AN14") (pintype "passive+no_connect"))
    )
    (net (code "65") (name "unconnected-(U2B-TEST_GPIO[12]_1-PadAR14)") (class "Default")
      (node (ref "U2") (pin "AR14") (pinfunction "TEST_GPIO[12]_1_AR14") (pintype "passive+no_connect"))
    )
    (net (code "66") (name "unconnected-(U2B-TEST_GPIO[13]_1-PadAR13)") (class "Default")
      (node (ref "U2") (pin "AR13") (pinfunction "TEST_GPIO[13]_1_AR13") (pintype "passive+no_connect"))
    )
    (net (code "67") (name "unconnected-(U2B-TEST_GPIO[14]_1-PadAT14)") (class "Default")
      (node (ref "U2") (pin "AT14") (pinfunction "TEST_GPIO[14]_1_AT14") (pintype "passive+no_connect"))
    )
    (net (code "68") (name "unconnected-(U2B-TEST_GPIO[15]_1-PadAP13)") (class "Default")
      (node (ref "U2") (pin "AP13") (pinfunction "TEST_GPIO[15]_1_AP13") (pintype "passive+no_connect"))
    )
    (net (code "69") (name "unconnected-(U2B-TEST_GPIO[16]_1-PadAP11)") (class "Default")
      (node (ref "U2") (pin "AP11") (pinfunction "TEST_GPIO[16]_1_AP11") (pintype "passive+no_connect"))
    )
    (net (code "70") (name "unconnected-(U2B-TEST_GPIO[17]_1-PadAT10)") (class "Default")
      (node (ref "U2") (pin "AT10") (pinfunction "TEST_GPIO[17]_1_AT10") (pintype "passive+no_connect"))
    )
    (net (code "71") (name "unconnected-(U2B-TEST_GPIO[18]_1-PadAR10)") (class "Default")
      (node (ref "U2") (pin "AR10") (pinfunction "TEST_GPIO[18]_1_AR10") (pintype "passive+no_connect"))
    )
    (net (code "72") (name "unconnected-(U2B-TEST_GPIO[19]_1-PadAN10)") (class "Default")
      (node (ref "U2") (pin "AN10") (pinfunction "TEST_GPIO[19]_1_AN10") (pintype "passive+no_connect"))
    )
    (net (code "73") (name "unconnected-(U2B-TEST_GPIO[20]_1-PadAP10)") (class "Default")
      (node (ref "U2") (pin "AP10") (pinfunction "TEST_GPIO[20]_1_AP10") (pintype "passive+no_connect"))
    )
    (net (code "74") (name "unconnected-(U2B-TEST_GPIO[21]_1-PadAT9)") (class "Default")
      (node (ref "U2") (pin "AT9") (pinfunction "TEST_GPIO[21]_1_AT9") (pintype "passive+no_connect"))
    )
    (net (code "75") (name "unconnected-(U2B-TEST_GPIO[22]_1-PadAR9)") (class "Default")
      (node (ref "U2") (pin "AR9") (pinfunction "TEST_GPIO[22]_1_AR9") (pintype "passive+no_connect"))
    )
    (net (code "76") (name "unconnected-(U2B-TEST_GPIO[23]_1-PadAR8)") (class "Default")
      (node (ref "U2") (pin "AR8") (pinfunction "TEST_GPIO[23]_1_AR8") (pintype "passive+no_connect"))
    )
    (net (code "77") (name "unconnected-(U2B-TEST_GPIO[24]_1-PadAN9)") (class "Default")
      (node (ref "U2") (pin "AN9") (pinfunction "TEST_GPIO[24]_1_AN9") (pintype "passive+no_connect"))
    )
    (net (code "78") (name "unconnected-(U2B-TEST_GPIO[25]_1-PadAP8)") (class "Default")
      (node (ref "U2") (pin "AP8") (pinfunction "TEST_GPIO[25]_1_AP8") (pintype "passive+no_connect"))
    )
    (net (code "79") (name "unconnected-(U2B-TEST_GPIO[26]_1-PadAN8)") (class "Default")
      (node (ref "U2") (pin "AN8") (pinfunction "TEST_GPIO[26]_1_AN8") (pintype "passive+no_connect"))
    )
    (net (code "80") (name "unconnected-(U2B-TEST_GPIO[27]_1-PadAR7)") (class "Default")
      (node (ref "U2") (pin "AR7") (pinfunction "TEST_GPIO[27]_1_AR7") (pintype "passive+no_connect"))
    )
    (net (code "81") (name "unconnected-(U2B-TEST_GPIO[28]_1-PadAT7)") (class "Default")
      (node (ref "U2") (pin "AT7") (pinfunction "TEST_GPIO[28]_1_AT7") (pintype "passive+no_connect"))
    )
    (net (code "82") (name "unconnected-(U2B-TEST_GPIO[29]_1-PadAP7)") (class "Default")
      (node (ref "U2") (pin "AP7") (pinfunction "TEST_GPIO[29]_1_AP7") (pintype "passive+no_connect"))
    )
    (net (code "83") (name "unconnected-(U2B-TEST_GPIO[30]_1-PadAT6)") (class "Default")
      (node (ref "U2") (pin "AT6") (pinfunction "TEST_GPIO[30]_1_AT6") (pintype "passive+no_connect"))
    )
    (net (code "84") (name "unconnected-(U2B-TEST_GPIO[31]_1-PadAT5)") (class "Default")
      (node (ref "U2") (pin "AT5") (pinfunction "TEST_GPIO[31]_1_AT5") (pintype "passive+no_connect"))
    )
    (net (code "85") (name "unconnected-(U2B-TEST_GPIO[32]_1-PadAP6)") (class "Default")
      (node (ref "U2") (pin "AP6") (pinfunction "TEST_GPIO[32]_1_AP6") (pintype "passive+no_connect"))
    )
    (net (code "86") (name "unconnected-(U2B-TEST_GPIO[33]_1-PadAN6)") (class "Default")
      (node (ref "U2") (pin "AN6") (pinfunction "TEST_GPIO[33]_1_AN6") (pintype "passive+no_connect"))
    )
    (net (code "87") (name "unconnected-(U2B-TEST_GPIO[34]_1-PadAN5)") (class "Default")
      (node (ref "U2") (pin "AN5") (pinfunction "TEST_GPIO[34]_1_AN5") (pintype "passive+no_connect"))
    )
    (net (code "88") (name "unconnected-(U2B-TEST_GPIO[35]_1-PadAT4)") (class "Default")
      (node (ref "U2") (pin "AT4") (pinfunction "TEST_GPIO[35]_1_AT4") (pintype "passive+no_connect"))
    )
    (net (code "89") (name "unconnected-(U2B-TEST_GPIO[36]_1-PadAR4)") (class "Default")
      (node (ref "U2") (pin "AR4") (pinfunction "TEST_GPIO[36]_1_AR4") (pintype "passive+no_connect"))
    )
    (net (code "90") (name "unconnected-(U2B-TEST_GPIO[37]_1-PadAN4)") (class "Default")
      (node (ref "U2") (pin "AN4") (pinfunction "TEST_GPIO[37]_1_AN4") (pintype "passive+no_connect"))
    )
    (net (code "91") (name "unconnected-(U2B-TEST_GPIO[38]_1-PadAR3)") (class "Default")
      (node (ref "U2") (pin "AR3") (pinfunction "TEST_GPIO[38]_1_AR3") (pintype "passive+no_connect"))
    )
    (net (code "92") (name "unconnected-(U2B-TEST_GPIO[39]_1-PadAM4)") (class "Default")
      (node (ref "U2") (pin "AM4") (pinfunction "TEST_GPIO[39]_1_AM4") (pintype "passive+no_connect"))
    )
    (net (code "93") (name "unconnected-(U2B-TEST_GPIO[40]_1-PadAP3)") (class "Default")
      (node (ref "U2") (pin "AP3") (pinfunction "TEST_GPIO[40]_1_AP3") (pintype "passive+no_connect"))
    )
    (net (code "94") (name "unconnected-(U2B-TEST_GPIO[41]_1-PadAN3)") (class "Default")
      (node (ref "U2") (pin "AN3") (pinfunction "TEST_GPIO[41]_1_AN3") (pintype "passive+no_connect"))
    )
    (net (code "95") (name "unconnected-(U2B-TEST_GPIO[42]_1-PadAR2)") (class "Default")
      (node (ref "U2") (pin "AR2") (pinfunction "TEST_GPIO[42]_1_AR2") (pintype "passive+no_connect"))
    )
    (net (code "96") (name "unconnected-(U2B-TEST_GPIO[43]_1-PadAL4)") (class "Default")
      (node (ref "U2") (pin "AL4") (pinfunction "TEST_GPIO[43]_1_AL4") (pintype "passive+no_connect"))
    )
    (net (code "97") (name "unconnected-(U2B-TEST_GPIO[44]_1-PadAM3)") (class "Default")
      (node (ref "U2") (pin "AM3") (pinfunction "TEST_GPIO[44]_1_AM3") (pintype "passive+no_connect"))
    )
    (net (code "98") (name "unconnected-(U2B-TEST_GPIO[45]_1-PadAP2)") (class "Default")
      (node (ref "U2") (pin "AP2") (pinfunction "TEST_GPIO[45]_1_AP2") (pintype "passive+no_connect"))
    )
    (net (code "99") (name "unconnected-(U2B-TEST_GPIO[46]_1-PadAP1)") (class "Default")
      (node (ref "U2") (pin "AP1") (pinfunction "TEST_GPIO[46]_1_AP1") (pintype "passive+no_connect"))
    )
    (net (code "100") (name "unconnected-(U2B-TEST_GPIO[47]_1-PadAK4)") (class "Default")
      (node (ref "U2") (pin "AK4") (pinfunction "TEST_GPIO[47]_1_AK4") (pintype "passive+no_connect"))
    )
    (net (code "101") (name "unconnected-(U2B-TEST_GPIO[48]_1-PadAM2)") (class "Default")
      (node (ref "U2") (pin "AM2") (pinfunction "TEST_GPIO[48]_1_AM2") (pintype "passive+no_connect"))
    )
    (net (code "102") (name "unconnected-(U2B-TEST_GPIO[49]_1-PadAN1)") (class "Default")
      (node (ref "U2") (pin "AN1") (pinfunction "TEST_GPIO[49]_1_AN1") (pintype "passive+no_connect"))
    )
    (net (code "103") (name "unconnected-(U2B-TEST_GPIO[50]_1-PadAK3)") (class "Default")
      (node (ref "U2") (pin "AK3") (pinfunction "TEST_GPIO[50]_1_AK3") (pintype "passive+no_connect"))
    )
    (net (code "104") (name "unconnected-(U2B-TEST_GPIO[51]_1-PadAL2)") (class "Default")
      (node (ref "U2") (pin "AL2") (pinfunction "TEST_GPIO[51]_1_AL2") (pintype "passive+no_connect"))
    )
    (net (code "105") (name "unconnected-(U2B-TEST_GPIO[52]_1-PadAD3)") (class "Default")
      (node (ref "U2") (pin "AD3") (pinfunction "TEST_GPIO[52]_1_AD3") (pintype "passive+no_connect"))
    )
    (net (code "106") (name "unconnected-(U2B-TEST_GPIO[53]_1-PadAD2)") (class "Default")
      (node (ref "U2") (pin "AD2") (pinfunction "TEST_GPIO[53]_1_AD2") (pintype "passive+no_connect"))
    )
    (net (code "107") (name "unconnected-(U2B-TEST_GPIO[54]_1-PadAC3)") (class "Default")
      (node (ref "U2") (pin "AC3") (pinfunction "TEST_GPIO[54]_1_AC3") (pintype "passive+no_connect"))
    )
    (net (code "108") (name "unconnected-(U2B-TEST_GPIO[55]_1-PadAC4)") (class "Default")
      (node (ref "U2") (pin "AC4") (pinfunction "TEST_GPIO[55]_1_AC4") (pintype "passive+no_connect"))
    )
    (net (code "109") (name "unconnected-(U2B-TEST_GPIO[56]_1-PadAD1)") (class "Default")
      (node (ref "U2") (pin "AD1") (pinfunction "TEST_GPIO[56]_1_AD1") (pintype "passive+no_connect"))
    )
    (net (code "110") (name "unconnected-(U2B-TEST_GPIO[57]_1-PadAC1)") (class "Default")
      (node (ref "U2") (pin "AC1") (pinfunction "TEST_GPIO[57]_1_AC1") (pintype "passive+no_connect"))
    )
    (net (code "111") (name "unconnected-(U2B-TEST_GPIO[58]_1-PadAB3)") (class "Default")
      (node (ref "U2") (pin "AB3") (pinfunction "TEST_GPIO[58]_1_AB3") (pintype "passive+no_connect"))
    )
    (net (code "112") (name "unconnected-(U2B-TEST_GPIO[59]_1-PadAB4)") (class "Default")
      (node (ref "U2") (pin "AB4") (pinfunction "TEST_GPIO[59]_1_AB4") (pintype "passive+no_connect"))
    )
    (net (code "113") (name "unconnected-(U2B-TEST_GPIO[60]_1-PadAB2)") (class "Default")
      (node (ref "U2") (pin "AB2") (pinfunction "TEST_GPIO[60]_1_AB2") (pintype "passive+no_connect"))
    )
    (net (code "114") (name "unconnected-(U2B-TEST_GPIO[61]_1-PadAA1)") (class "Default")
      (node (ref "U2") (pin "AA1") (pinfunction "TEST_GPIO[61]_1_AA1") (pintype "passive+no_connect"))
    )
    (net (code "115") (name "unconnected-(U2B-TEST_GPIO[62]_1-PadAB1)") (class "Default")
      (node (ref "U2") (pin "AB1") (pinfunction "TEST_GPIO[62]_1_AB1") (pintype "passive+no_connect"))
    )
    (net (code "116") (name "unconnected-(U2B-TEST_GPIO[63]_1-PadAA2)") (class "Default")
      (node (ref "U2") (pin "AA2") (pinfunction "TEST_GPIO[63]_1_AA2") (pintype "passive+no_connect"))
    )
    (net (code "117") (name "unconnected-(U2B-TEST_GPIO[64]_1-PadAA4)") (class "Default")
      (node (ref "U2") (pin "AA4") (pinfunction "TEST_GPIO[64]_1_AA4") (pintype "passive+no_connect"))
    )
    (net (code "118") (name "unconnected-(U2B-TEST_GPIO[65]_1-PadY3)") (class "Default")
      (node (ref "U2") (pin "Y3") (pinfunction "TEST_GPIO[65]_1_Y3") (pintype "passive+no_connect"))
    )
    (net (code "119") (name "unconnected-(U2B-TEST_GPIO[66]_1-PadY2)") (class "Default")
      (node (ref "U2") (pin "Y2") (pinfunction "TEST_GPIO[66]_1_Y2") (pintype "passive+no_connect"))
    )
    (net (code "120") (name "unconnected-(U2B-TEST_GPIO[67]_1-PadY4)") (class "Default")
      (node (ref "U2") (pin "Y4") (pinfunction "TEST_GPIO[67]_1_Y4") (pintype "passive+no_connect"))
    )
    (net (code "121") (name "unconnected-(U2B-TEST_GPIO[68]_1-PadW1)") (class "Default")
      (node (ref "U2") (pin "W1") (pinfunction "TEST_GPIO[68]_1_W1") (pintype "passive+no_connect"))
    )
    (net (code "122") (name "unconnected-(U2B-TEST_GPIO[69]_1-PadW3)") (class "Default")
      (node (ref "U2") (pin "W3") (pinfunction "TEST_GPIO[69]_1_W3") (pintype "passive+no_connect"))
    )
    (net (code "123") (name "unconnected-(U2B-TEST_GPIO[70]_1-PadW2)") (class "Default")
      (node (ref "U2") (pin "W2") (pinfunction "TEST_GPIO[70]_1_W2") (pintype "passive+no_connect"))
    )
    (net (code "124") (name "unconnected-(U2B-TEST_GPIO[71]_1-PadW5)") (class "Default")
      (node (ref "U2") (pin "W5") (pinfunction "TEST_GPIO[71]_1_W5") (pintype "passive+no_connect"))
    )
    (net (code "125") (name "unconnected-(U2C-DBG_SPARE[0]_2-PadAP25)") (class "Default")
      (node (ref "U2") (pin "AP25") (pinfunction "DBG_SPARE[0]_2_AP25") (pintype "passive+no_connect"))
    )
    (net (code "126") (name "unconnected-(U2C-DBG_SPARE[1]_2-PadAR25)") (class "Default")
      (node (ref "U2") (pin "AR25") (pinfunction "DBG_SPARE[1]_2_AR25") (pintype "passive+no_connect"))
    )
    (net (code "127") (name "unconnected-(U2C-JTG_TCK_2-PadAF33)") (class "Default")
      (node (ref "U2") (pin "AF33") (pinfunction "JTG_TCK_2_AF33") (pintype "passive+no_connect"))
    )
    (net (code "128") (name "unconnected-(U2C-JTG_TDI_2-PadAF36)") (class "Default")
      (node (ref "U2") (pin "AF36") (pinfunction "JTG_TDI_2_AF36") (pintype "passive+no_connect"))
    )
    (net (code "129") (name "unconnected-(U2C-JTG_TDO_2-PadAE34)") (class "Default")
      (node (ref "U2") (pin "AE34") (pinfunction "JTG_TDO_2_AE34") (pintype "passive+no_connect"))
    )
    (net (code "130") (name "unconnected-(U2C-JTG_TMS_2-PadAE36)") (class "Default")
      (node (ref "U2") (pin "AE36") (pinfunction "JTG_TMS_2_AE36") (pintype "passive+no_connect"))
    )
    (net (code "131") (name "unconnected-(U2C-TEST_GPIO[0]_2-PadW35)") (class "Default")
      (node (ref "U2") (pin "W35") (pinfunction "TEST_GPIO[0]_2_W35") (pintype "passive+no_connect"))
    )
    (net (code "132") (name "unconnected-(U2C-TEST_GPIO[1]_2-PadY35)") (class "Default")
      (node (ref "U2") (pin "Y35") (pinfunction "TEST_GPIO[1]_2_Y35") (pintype "passive+no_connect"))
    )
    (net (code "133") (name "unconnected-(U2C-TEST_GPIO[2]_2-PadY34)") (class "Default")
      (node (ref "U2") (pin "Y34") (pinfunction "TEST_GPIO[2]_2_Y34") (pintype "passive+no_connect"))
    )
    (net (code "134") (name "unconnected-(U2C-TEST_GPIO[3]_2-PadY36)") (class "Default")
      (node (ref "U2") (pin "Y36") (pinfunction "TEST_GPIO[3]_2_Y36") (pintype "passive+no_connect"))
    )
    (net (code "135") (name "unconnected-(U2C-TEST_GPIO[4]_2-PadAA33)") (class "Default")
      (node (ref "U2") (pin "AA33") (pinfunction "TEST_GPIO[4]_2_AA33") (pintype "passive+no_connect"))
    )
    (net (code "136") (name "unconnected-(U2C-TEST_GPIO[5]_2-PadAA36)") (class "Default")
      (node (ref "U2") (pin "AA36") (pinfunction "TEST_GPIO[5]_2_AA36") (pintype "passive+no_connect"))
    )
    (net (code "137") (name "unconnected-(U2C-TEST_GPIO[6]_2-PadAA34)") (class "Default")
      (node (ref "U2") (pin "AA34") (pinfunction "TEST_GPIO[6]_2_AA34") (pintype "passive+no_connect"))
    )
    (net (code "138") (name "unconnected-(U2C-TEST_GPIO[7]_2-PadAB33)") (class "Default")
      (node (ref "U2") (pin "AB33") (pinfunction "TEST_GPIO[7]_2_AB33") (pintype "passive+no_connect"))
    )
    (net (code "139") (name "unconnected-(U2C-TEST_GPIO[8]_2-PadAB34)") (class "Default")
      (node (ref "U2") (pin "AB34") (pinfunction "TEST_GPIO[8]_2_AB34") (pintype "passive+no_connect"))
    )
    (net (code "140") (name "unconnected-(U2C-TEST_GPIO[9]_2-PadAB36)") (class "Default")
      (node (ref "U2") (pin "AB36") (pinfunction "TEST_GPIO[9]_2_AB36") (pintype "passive+no_connect"))
    )
    (net (code "141") (name "unconnected-(U2C-TEST_GPIO[10]_2-PadAB35)") (class "Default")
      (node (ref "U2") (pin "AB35") (pinfunction "TEST_GPIO[10]_2_AB35") (pintype "passive+no_connect"))
    )
    (net (code "142") (name "unconnected-(U2C-TEST_GPIO[11]_2-PadAC33)") (class "Default")
      (node (ref "U2") (pin "AC33") (pinfunction "TEST_GPIO[11]_2_AC33") (pintype "passive+no_connect"))
    )
    (net (code "143") (name "unconnected-(U2C-TEST_GPIO[12]_2-PadAC35)") (class "Default")
      (node (ref "U2") (pin "AC35") (pinfunction "TEST_GPIO[12]_2_AC35") (pintype "passive+no_connect"))
    )
    (net (code "144") (name "unconnected-(U2C-TEST_GPIO[13]_2-PadAD35)") (class "Default")
      (node (ref "U2") (pin "AD35") (pinfunction "TEST_GPIO[13]_2_AD35") (pintype "passive+no_connect"))
    )
    (net (code "145") (name "unconnected-(U2C-TEST_GPIO[14]_2-PadAC36)") (class "Default")
      (node (ref "U2") (pin "AC36") (pinfunction "TEST_GPIO[14]_2_AC36") (pintype "passive+no_connect"))
    )
    (net (code "146") (name "unconnected-(U2C-TEST_GPIO[15]_2-PadAD34)") (class "Default")
      (node (ref "U2") (pin "AD34") (pinfunction "TEST_GPIO[15]_2_AD34") (pintype "passive+no_connect"))
    )
    (net (code "147") (name "unconnected-(U2C-TEST_GPIO[16]_2-PadAF34)") (class "Default")
      (node (ref "U2") (pin "AF34") (pinfunction "TEST_GPIO[16]_2_AF34") (pintype "passive+no_connect"))
    )
    (net (code "148") (name "unconnected-(U2C-TEST_GPIO[17]_2-PadAG36)") (class "Default")
      (node (ref "U2") (pin "AG36") (pinfunction "TEST_GPIO[17]_2_AG36") (pintype "passive+no_connect"))
    )
    (net (code "149") (name "unconnected-(U2C-TEST_GPIO[18]_2-PadAG35)") (class "Default")
      (node (ref "U2") (pin "AG35") (pinfunction "TEST_GPIO[18]_2_AG35") (pintype "passive+no_connect"))
    )
    (net (code "150") (name "unconnected-(U2C-TEST_GPIO[19]_2-PadAG33)") (class "Default")
      (node (ref "U2") (pin "AG33") (pinfunction "TEST_GPIO[19]_2_AG33") (pintype "passive+no_connect"))
    )
    (net (code "151") (name "unconnected-(U2C-TEST_GPIO[20]_2-PadAG34)") (class "Default")
      (node (ref "U2") (pin "AG34") (pinfunction "TEST_GPIO[20]_2_AG34") (pintype "passive+no_connect"))
    )
    (net (code "152") (name "unconnected-(U2C-TEST_GPIO[21]_2-PadAH36)") (class "Default")
      (node (ref "U2") (pin "AH36") (pinfunction "TEST_GPIO[21]_2_AH36") (pintype "passive+no_connect"))
    )
    (net (code "153") (name "unconnected-(U2C-TEST_GPIO[22]_2-PadAH35)") (class "Default")
      (node (ref "U2") (pin "AH35") (pinfunction "TEST_GPIO[22]_2_AH35") (pintype "passive+no_connect"))
    )
    (net (code "154") (name "unconnected-(U2C-TEST_GPIO[23]_2-PadAJ35)") (class "Default")
      (node (ref "U2") (pin "AJ35") (pinfunction "TEST_GPIO[23]_2_AJ35") (pintype "passive+no_connect"))
    )
    (net (code "155") (name "unconnected-(U2C-TEST_GPIO[24]_2-PadAH33)") (class "Default")
      (node (ref "U2") (pin "AH33") (pinfunction "TEST_GPIO[24]_2_AH33") (pintype "passive+no_connect"))
    )
    (net (code "156") (name "unconnected-(U2C-TEST_GPIO[25]_2-PadAJ34)") (class "Default")
      (node (ref "U2") (pin "AJ34") (pinfunction "TEST_GPIO[25]_2_AJ34") (pintype "passive+no_connect"))
    )
    (net (code "157") (name "unconnected-(U2C-TEST_GPIO[26]_2-PadAJ33)") (class "Default")
      (node (ref "U2") (pin "AJ33") (pinfunction "TEST_GPIO[26]_2_AJ33") (pintype "passive+no_connect"))
    )
    (net (code "158") (name "unconnected-(U2C-TEST_GPIO[27]_2-PadAK35)") (class "Default")
      (node (ref "U2") (pin "AK35") (pinfunction "TEST_GPIO[27]_2_AK35") (pintype "passive+no_connect"))
    )
    (net (code "159") (name "unconnected-(U2C-TEST_GPIO[28]_2-PadAK36)") (class "Default")
      (node (ref "U2") (pin "AK36") (pinfunction "TEST_GPIO[28]_2_AK36") (pintype "passive+no_connect"))
    )
    (net (code "160") (name "unconnected-(U2C-TEST_GPIO[29]_2-PadAK34)") (class "Default")
      (node (ref "U2") (pin "AK34") (pinfunction "TEST_GPIO[29]_2_AK34") (pintype "passive+no_connect"))
    )
    (net (code "161") (name "unconnected-(U2C-TEST_GPIO[30]_2-PadAL36)") (class "Default")
      (node (ref "U2") (pin "AL36") (pinfunction "TEST_GPIO[30]_2_AL36") (pintype "passive+no_connect"))
    )
    (net (code "162") (name "unconnected-(U2C-TEST_GPIO[31]_2-PadAM36)") (class "Default")
      (node (ref "U2") (pin "AM36") (pinfunction "TEST_GPIO[31]_2_AM36") (pintype "passive+no_connect"))
    )
    (net (code "163") (name "unconnected-(U2C-TEST_GPIO[32]_2-PadAL34)") (class "Default")
      (node (ref "U2") (pin "AL34") (pinfunction "TEST_GPIO[32]_2_AL34") (pintype "passive+no_connect"))
    )
    (net (code "164") (name "unconnected-(U2C-TEST_GPIO[33]_2-PadAL33)") (class "Default")
      (node (ref "U2") (pin "AL33") (pinfunction "TEST_GPIO[33]_2_AL33") (pintype "passive+no_connect"))
    )
    (net (code "165") (name "unconnected-(U2C-TEST_GPIO[34]_2-PadAM33)") (class "Default")
      (node (ref "U2") (pin "AM33") (pinfunction "TEST_GPIO[34]_2_AM33") (pintype "passive+no_connect"))
    )
    (net (code "166") (name "unconnected-(U2C-TEST_GPIO[35]_2-PadAN36)") (class "Default")
      (node (ref "U2") (pin "AN36") (pinfunction "TEST_GPIO[35]_2_AN36") (pintype "passive+no_connect"))
    )
    (net (code "167") (name "unconnected-(U2C-TEST_GPIO[36]_2-PadAN35)") (class "Default")
      (node (ref "U2") (pin "AN35") (pinfunction "TEST_GPIO[36]_2_AN35") (pintype "passive+no_connect"))
    )
    (net (code "168") (name "unconnected-(U2C-TEST_GPIO[37]_2-PadAN33)") (class "Default")
      (node (ref "U2") (pin "AN33") (pinfunction "TEST_GPIO[37]_2_AN33") (pintype "passive+no_connect"))
    )
    (net (code "169") (name "unconnected-(U2C-TEST_GPIO[38]_2-PadAP35)") (class "Default")
      (node (ref "U2") (pin "AP35") (pinfunction "TEST_GPIO[38]_2_AP35") (pintype "passive+no_connect"))
    )
    (net (code "170") (name "unconnected-(U2C-TEST_GPIO[39]_2-PadAN32)") (class "Default")
      (node (ref "U2") (pin "AN32") (pinfunction "TEST_GPIO[39]_2_AN32") (pintype "passive+no_connect"))
    )
    (net (code "171") (name "unconnected-(U2C-TEST_GPIO[40]_2-PadAP34)") (class "Default")
      (node (ref "U2") (pin "AP34") (pinfunction "TEST_GPIO[40]_2_AP34") (pintype "passive+no_connect"))
    )
    (net (code "172") (name "unconnected-(U2C-TEST_GPIO[41]_2-PadAP33)") (class "Default")
      (node (ref "U2") (pin "AP33") (pinfunction "TEST_GPIO[41]_2_AP33") (pintype "passive+no_connect"))
    )
    (net (code "173") (name "unconnected-(U2C-TEST_GPIO[42]_2-PadAR35)") (class "Default")
      (node (ref "U2") (pin "AR35") (pinfunction "TEST_GPIO[42]_2_AR35") (pintype "passive+no_connect"))
    )
    (net (code "174") (name "unconnected-(U2C-TEST_GPIO[43]_2-PadAN31)") (class "Default")
      (node (ref "U2") (pin "AN31") (pinfunction "TEST_GPIO[43]_2_AN31") (pintype "passive+no_connect"))
    )
    (net (code "175") (name "unconnected-(U2C-TEST_GPIO[44]_2-PadAP32)") (class "Default")
      (node (ref "U2") (pin "AP32") (pinfunction "TEST_GPIO[44]_2_AP32") (pintype "passive+no_connect"))
    )
    (net (code "176") (name "unconnected-(U2C-TEST_GPIO[45]_2-PadAR34)") (class "Default")
      (node (ref "U2") (pin "AR34") (pinfunction "TEST_GPIO[45]_2_AR34") (pintype "passive+no_connect"))
    )
    (net (code "177") (name "unconnected-(U2C-TEST_GPIO[46]_2-PadAT34)") (class "Default")
      (node (ref "U2") (pin "AT34") (pinfunction "TEST_GPIO[46]_2_AT34") (pintype "passive+no_connect"))
    )
    (net (code "178") (name "unconnected-(U2C-TEST_GPIO[47]_2-PadAN30)") (class "Default")
      (node (ref "U2") (pin "AN30") (pinfunction "TEST_GPIO[47]_2_AN30") (pintype "passive+no_connect"))
    )
    (net (code "179") (name "unconnected-(U2C-TEST_GPIO[48]_2-PadAR32)") (class "Default")
      (node (ref "U2") (pin "AR32") (pinfunction "TEST_GPIO[48]_2_AR32") (pintype "passive+no_connect"))
    )
    (net (code "180") (name "unconnected-(U2C-TEST_GPIO[49]_2-PadAT33)") (class "Default")
      (node (ref "U2") (pin "AT33") (pinfunction "TEST_GPIO[49]_2_AT33") (pintype "passive+no_connect"))
    )
    (net (code "181") (name "unconnected-(U2C-TEST_GPIO[50]_2-PadAP30)") (class "Default")
      (node (ref "U2") (pin "AP30") (pinfunction "TEST_GPIO[50]_2_AP30") (pintype "passive+no_connect"))
    )
    (net (code "182") (name "unconnected-(U2C-TEST_GPIO[51]_2-PadAR31)") (class "Default")
      (node (ref "U2") (pin "AR31") (pinfunction "TEST_GPIO[51]_2_AR31") (pintype "passive+no_connect"))
    )
    (net (code "183") (name "unconnected-(U2C-TEST_GPIO[52]_2-PadAP24)") (class "Default")
      (node (ref "U2") (pin "AP24") (pinfunction "TEST_GPIO[52]_2_AP24") (pintype "passive+no_connect"))
    )
    (net (code "184") (name "unconnected-(U2C-TEST_GPIO[53]_2-PadAR24)") (class "Default")
      (node (ref "U2") (pin "AR24") (pinfunction "TEST_GPIO[53]_2_AR24") (pintype "passive+no_connect"))
    )
    (net (code "185") (name "unconnected-(U2C-TEST_GPIO[54]_2-PadAP23)") (class "Default")
      (node (ref "U2") (pin "AP23") (pinfunction "TEST_GPIO[54]_2_AP23") (pintype "passive+no_connect"))
    )
    (net (code "186") (name "unconnected-(U2C-TEST_GPIO[55]_2-PadAN23)") (class "Default")
      (node (ref "U2") (pin "AN23") (pinfunction "TEST_GPIO[55]_2_AN23") (pintype "passive+no_connect"))
    )
    (net (code "187") (name "unconnected-(U2C-TEST_GPIO[56]_2-PadAT24)") (class "Default")
      (node (ref "U2") (pin "AT24") (pinfunction "TEST_GPIO[56]_2_AT24") (pintype "passive+no_connect"))
    )
    (net (code "188") (name "unconnected-(U2C-TEST_GPIO[57]_2-PadAT23)") (class "Default")
      (node (ref "U2") (pin "AT23") (pinfunction "TEST_GPIO[57]_2_AT23") (pintype "passive+no_connect"))
    )
    (net (code "189") (name "unconnected-(U2C-TEST_GPIO[58]_2-PadAP22)") (class "Default")
      (node (ref "U2") (pin "AP22") (pinfunction "TEST_GPIO[58]_2_AP22") (pintype "passive+no_connect"))
    )
    (net (code "190") (name "unconnected-(U2C-TEST_GPIO[59]_2-PadAN22)") (class "Default")
      (node (ref "U2") (pin "AN22") (pinfunction "TEST_GPIO[59]_2_AN22") (pintype "passive+no_connect"))
    )
    (net (code "191") (name "unconnected-(U2C-TEST_GPIO[60]_2-PadAR22)") (class "Default")
      (node (ref "U2") (pin "AR22") (pinfunction "TEST_GPIO[60]_2_AR22") (pintype "passive+no_connect"))
    )
    (net (code "192") (name "unconnected-(U2C-TEST_GPIO[61]_2-PadAT21)") (class "Default")
      (node (ref "U2") (pin "AT21") (pinfunction "TEST_GPIO[61]_2_AT21") (pintype "passive+no_connect"))
    )
    (net (code "193") (name "unconnected-(U2C-TEST_GPIO[62]_2-PadAT22)") (class "Default")
      (node (ref "U2") (pin "AT22") (pinfunction "TEST_GPIO[62]_2_AT22") (pintype "passive+no_connect"))
    )
    (net (code "194") (name "unconnected-(U2C-TEST_GPIO[63]_2-PadAR21)") (class "Default")
      (node (ref "U2") (pin "AR21") (pinfunction "TEST_GPIO[63]_2_AR21") (pintype "passive+no_connect"))
    )
    (net (code "195") (name "unconnected-(U2C-TEST_GPIO[64]_2-PadAN21)") (class "Default")
      (node (ref "U2") (pin "AN21") (pinfunction "TEST_GPIO[64]_2_AN21") (pintype "passive+no_connect"))
    )
    (net (code "196") (name "unconnected-(U2C-TEST_GPIO[65]_2-PadAP20)") (class "Default")
      (node (ref "U2") (pin "AP20") (pinfunction "TEST_GPIO[65]_2_AP20") (pintype "passive+no_connect"))
    )
    (net (code "197") (name "unconnected-(U2C-TEST_GPIO[66]_2-PadAR20)") (class "Default")
      (node (ref "U2") (pin "AR20") (pinfunction "TEST_GPIO[66]_2_AR20") (pintype "passive+no_connect"))
    )
    (net (code "198") (name "unconnected-(U2C-TEST_GPIO[67]_2-PadAN20)") (class "Default")
      (node (ref "U2") (pin "AN20") (pinfunction "TEST_GPIO[67]_2_AN20") (pintype "passive+no_connect"))
    )
    (net (code "199") (name "unconnected-(U2C-TEST_GPIO[68]_2-PadAT19)") (class "Default")
      (node (ref "U2") (pin "AT19") (pinfunction "TEST_GPIO[68]_2_AT19") (pintype "passive+no_connect"))
    )
    (net (code "200") (name "unconnected-(U2C-TEST_GPIO[69]_2-PadAP19)") (class "Default")
      (node (ref "U2") (pin "AP19") (pinfunction "TEST_GPIO[69]_2_AP19") (pintype "passive+no_connect"))
    )
    (net (code "201") (name "unconnected-(U2C-TEST_GPIO[70]_2-PadAR19)") (class "Default")
      (node (ref "U2") (pin "AR19") (pinfunction "TEST_GPIO[70]_2_AR19") (pintype "passive+no_connect"))
    )
    (net (code "202") (name "unconnected-(U2C-TEST_GPIO[71]_2-PadAM19)") (class "Default")
      (node (ref "U2") (pin "AM19") (pinfunction "TEST_GPIO[71]_2_AM19") (pintype "passive+no_connect"))
    )
    (net (code "203") (name "unconnected-(U2D-DBG_SPARE[0]_3-PadM34)") (class "Default")
      (node (ref "U2") (pin "M34") (pinfunction "DBG_SPARE[0]_3_M34") (pintype "passive+no_connect"))
    )
    (net (code "204") (name "unconnected-(U2D-DBG_SPARE[1]_3-PadM35)") (class "Default")
      (node (ref "U2") (pin "M35") (pinfunction "DBG_SPARE[1]_3_M35") (pintype "passive+no_connect"))
    )
    (net (code "205") (name "unconnected-(U2D-JTG_TCK_3-PadD26)") (class "Default")
      (node (ref "U2") (pin "D26") (pinfunction "JTG_TCK_3_D26") (pintype "passive+no_connect"))
    )
    (net (code "206") (name "unconnected-(U2D-JTG_TDI_3-PadA26)") (class "Default")
      (node (ref "U2") (pin "A26") (pinfunction "JTG_TDI_3_A26") (pintype "passive+no_connect"))
    )
    (net (code "207") (name "unconnected-(U2D-JTG_TDO_3-PadC25)") (class "Default")
      (node (ref "U2") (pin "C25") (pinfunction "JTG_TDO_3_C25") (pintype "passive+no_connect"))
    )
    (net (code "208") (name "unconnected-(U2D-JTG_TMS_3-PadA25)") (class "Default")
      (node (ref "U2") (pin "A25") (pinfunction "JTG_TMS_3_A25") (pintype "passive+no_connect"))
    )
    (net (code "209") (name "unconnected-(U2D-TEST_GPIO[0]_3-PadB19)") (class "Default")
      (node (ref "U2") (pin "B19") (pinfunction "TEST_GPIO[0]_3_B19") (pintype "passive+no_connect"))
    )
    (net (code "210") (name "unconnected-(U2D-TEST_GPIO[1]_3-PadB20)") (class "Default")
      (node (ref "U2") (pin "B20") (pinfunction "TEST_GPIO[1]_3_B20") (pintype "passive+no_connect"))
    )
    (net (code "211") (name "unconnected-(U2D-TEST_GPIO[2]_3-PadC20)") (class "Default")
      (node (ref "U2") (pin "C20") (pinfunction "TEST_GPIO[2]_3_C20") (pintype "passive+no_connect"))
    )
    (net (code "212") (name "unconnected-(U2D-TEST_GPIO[3]_3-PadA20)") (class "Default")
      (node (ref "U2") (pin "A20") (pinfunction "TEST_GPIO[3]_3_A20") (pintype "passive+no_connect"))
    )
    (net (code "213") (name "unconnected-(U2D-TEST_GPIO[4]_3-PadD21)") (class "Default")
      (node (ref "U2") (pin "D21") (pinfunction "TEST_GPIO[4]_3_D21") (pintype "passive+no_connect"))
    )
    (net (code "214") (name "unconnected-(U2D-TEST_GPIO[5]_3-PadA21)") (class "Default")
      (node (ref "U2") (pin "A21") (pinfunction "TEST_GPIO[5]_3_A21") (pintype "passive+no_connect"))
    )
    (net (code "215") (name "unconnected-(U2D-TEST_GPIO[6]_3-PadC21)") (class "Default")
      (node (ref "U2") (pin "C21") (pinfunction "TEST_GPIO[6]_3_C21") (pintype "passive+no_connect"))
    )
    (net (code "216") (name "unconnected-(U2D-TEST_GPIO[7]_3-PadD22)") (class "Default")
      (node (ref "U2") (pin "D22") (pinfunction "TEST_GPIO[7]_3_D22") (pintype "passive+no_connect"))
    )
    (net (code "217") (name "unconnected-(U2D-TEST_GPIO[8]_3-PadC22)") (class "Default")
      (node (ref "U2") (pin "C22") (pinfunction "TEST_GPIO[8]_3_C22") (pintype "passive+no_connect"))
    )
    (net (code "218") (name "unconnected-(U2D-TEST_GPIO[9]_3-PadA22)") (class "Default")
      (node (ref "U2") (pin "A22") (pinfunction "TEST_GPIO[9]_3_A22") (pintype "passive+no_connect"))
    )
    (net (code "219") (name "unconnected-(U2D-TEST_GPIO[10]_3-PadB22)") (class "Default")
      (node (ref "U2") (pin "B22") (pinfunction "TEST_GPIO[10]_3_B22") (pintype "passive+no_connect"))
    )
    (net (code "220") (name "unconnected-(U2D-TEST_GPIO[11]_3-PadD23)") (class "Default")
      (node (ref "U2") (pin "D23") (pinfunction "TEST_GPIO[11]_3_D23") (pintype "passive+no_connect"))
    )
    (net (code "221") (name "unconnected-(U2D-TEST_GPIO[12]_3-PadB23)") (class "Default")
      (node (ref "U2") (pin "B23") (pinfunction "TEST_GPIO[12]_3_B23") (pintype "passive+no_connect"))
    )
    (net (code "222") (name "unconnected-(U2D-TEST_GPIO[13]_3-PadB24)") (class "Default")
      (node (ref "U2") (pin "B24") (pinfunction "TEST_GPIO[13]_3_B24") (pintype "passive+no_connect"))
    )
    (net (code "223") (name "unconnected-(U2D-TEST_GPIO[14]_3-PadA23)") (class "Default")
      (node (ref "U2") (pin "A23") (pinfunction "TEST_GPIO[14]_3_A23") (pintype "passive+no_connect"))
    )
    (net (code "224") (name "unconnected-(U2D-TEST_GPIO[15]_3-PadC24)") (class "Default")
      (node (ref "U2") (pin "C24") (pinfunction "TEST_GPIO[15]_3_C24") (pintype "passive+no_connect"))
    )
    (net (code "225") (name "unconnected-(U2D-TEST_GPIO[16]_3-PadC26)") (class "Default")
      (node (ref "U2") (pin "C26") (pinfunction "TEST_GPIO[16]_3_C26") (pintype "passive+no_connect"))
    )
    (net (code "226") (name "unconnected-(U2D-TEST_GPIO[17]_3-PadA27)") (class "Default")
      (node (ref "U2") (pin "A27") (pinfunction "TEST_GPIO[17]_3_A27") (pintype "passive+no_connect"))
    )
    (net (code "227") (name "unconnected-(U2D-TEST_GPIO[18]_3-PadB27)") (class "Default")
      (node (ref "U2") (pin "B27") (pinfunction "TEST_GPIO[18]_3_B27") (pintype "passive+no_connect"))
    )
    (net (code "228") (name "unconnected-(U2D-TEST_GPIO[19]_3-PadD27)") (class "Default")
      (node (ref "U2") (pin "D27") (pinfunction "TEST_GPIO[19]_3_D27") (pintype "passive+no_connect"))
    )
    (net (code "229") (name "unconnected-(U2D-TEST_GPIO[20]_3-PadC27)") (class "Default")
      (node (ref "U2") (pin "C27") (pinfunction "TEST_GPIO[20]_3_C27") (pintype "passive+no_connect"))
    )
    (net (code "230") (name "unconnected-(U2D-TEST_GPIO[21]_3-PadA28)") (class "Default")
      (node (ref "U2") (pin "A28") (pinfunction "TEST_GPIO[21]_3_A28") (pintype "passive+no_connect"))
    )
    (net (code "231") (name "unconnected-(U2D-TEST_GPIO[22]_3-PadB28)") (class "Default")
      (node (ref "U2") (pin "B28") (pinfunction "TEST_GPIO[22]_3_B28") (pintype "passive+no_connect"))
    )
    (net (code "232") (name "unconnected-(U2D-TEST_GPIO[23]_3-PadB29)") (class "Default")
      (node (ref "U2") (pin "B29") (pinfunction "TEST_GPIO[23]_3_B29") (pintype "passive+no_connect"))
    )
    (net (code "233") (name "unconnected-(U2D-TEST_GPIO[24]_3-PadD28)") (class "Default")
      (node (ref "U2") (pin "D28") (pinfunction "TEST_GPIO[24]_3_D28") (pintype "passive+no_connect"))
    )
    (net (code "234") (name "unconnected-(U2D-TEST_GPIO[25]_3-PadC29)") (class "Default")
      (node (ref "U2") (pin "C29") (pinfunction "TEST_GPIO[25]_3_C29") (pintype "passive+no_connect"))
    )
    (net (code "235") (name "unconnected-(U2D-TEST_GPIO[26]_3-PadD29)") (class "Default")
      (node (ref "U2") (pin "D29") (pinfunction "TEST_GPIO[26]_3_D29") (pintype "passive+no_connect"))
    )
    (net (code "236") (name "unconnected-(U2D-TEST_GPIO[27]_3-PadB30)") (class "Default")
      (node (ref "U2") (pin "B30") (pinfunction "TEST_GPIO[27]_3_B30") (pintype "passive+no_connect"))
    )
    (net (code "237") (name "unconnected-(U2D-TEST_GPIO[28]_3-PadA30)") (class "Default")
      (node (ref "U2") (pin "A30") (pinfunction "TEST_GPIO[28]_3_A30") (pintype "passive+no_connect"))
    )
    (net (code "238") (name "unconnected-(U2D-TEST_GPIO[29]_3-PadC30)") (class "Default")
      (node (ref "U2") (pin "C30") (pinfunction "TEST_GPIO[29]_3_C30") (pintype "passive+no_connect"))
    )
    (net (code "239") (name "unconnected-(U2D-TEST_GPIO[30]_3-PadA31)") (class "Default")
      (node (ref "U2") (pin "A31") (pinfunction "TEST_GPIO[30]_3_A31") (pintype "passive+no_connect"))
    )
    (net (code "240") (name "unconnected-(U2D-TEST_GPIO[31]_3-PadA32)") (class "Default")
      (node (ref "U2") (pin "A32") (pinfunction "TEST_GPIO[31]_3_A32") (pintype "passive+no_connect"))
    )
    (net (code "241") (name "unconnected-(U2D-TEST_GPIO[32]_3-PadC31)") (class "Default")
      (node (ref "U2") (pin "C31") (pinfunction "TEST_GPIO[32]_3_C31") (pintype "passive+no_connect"))
    )
    (net (code "242") (name "unconnected-(U2D-TEST_GPIO[33]_3-PadD31)") (class "Default")
      (node (ref "U2") (pin "D31") (pinfunction "TEST_GPIO[33]_3_D31") (pintype "passive+no_connect"))
    )
    (net (code "243") (name "unconnected-(U2D-TEST_GPIO[34]_3-PadD32)") (class "Default")
      (node (ref "U2") (pin "D32") (pinfunction "TEST_GPIO[34]_3_D32") (pintype "passive+no_connect"))
    )
    (net (code "244") (name "unconnected-(U2D-TEST_GPIO[35]_3-PadA33)") (class "Default")
      (node (ref "U2") (pin "A33") (pinfunction "TEST_GPIO[35]_3_A33") (pintype "passive+no_connect"))
    )
    (net (code "245") (name "unconnected-(U2D-TEST_GPIO[36]_3-PadB33)") (class "Default")
      (node (ref "U2") (pin "B33") (pinfunction "TEST_GPIO[36]_3_B33") (pintype "passive+no_connect"))
    )
    (net (code "246") (name "unconnected-(U2D-TEST_GPIO[37]_3-PadD33)") (class "Default")
      (node (ref "U2") (pin "D33") (pinfunction "TEST_GPIO[37]_3_D33") (pintype "passive+no_connect"))
    )
    (net (code "247") (name "unconnected-(U2D-TEST_GPIO[38]_3-PadB34)") (class "Default")
      (node (ref "U2") (pin "B34") (pinfunction "TEST_GPIO[38]_3_B34") (pintype "passive+no_connect"))
    )
    (net (code "248") (name "unconnected-(U2D-TEST_GPIO[39]_3-PadE33)") (class "Default")
      (node (ref "U2") (pin "E33") (pinfunction "TEST_GPIO[39]_3_E33") (pintype "passive+no_connect"))
    )
    (net (code "249") (name "unconnected-(U2D-TEST_GPIO[40]_3-PadC34)") (class "Default")
      (node (ref "U2") (pin "C34") (pinfunction "TEST_GPIO[40]_3_C34") (pintype "passive+no_connect"))
    )
    (net (code "250") (name "unconnected-(U2D-TEST_GPIO[41]_3-PadD34)") (class "Default")
      (node (ref "U2") (pin "D34") (pinfunction "TEST_GPIO[41]_3_D34") (pintype "passive+no_connect"))
    )
    (net (code "251") (name "unconnected-(U2D-TEST_GPIO[42]_3-PadB35)") (class "Default")
      (node (ref "U2") (pin "B35") (pinfunction "TEST_GPIO[42]_3_B35") (pintype "passive+no_connect"))
    )
    (net (code "252") (name "unconnected-(U2D-TEST_GPIO[43]_3-PadF33)") (class "Default")
      (node (ref "U2") (pin "F33") (pinfunction "TEST_GPIO[43]_3_F33") (pintype "passive+no_connect"))
    )
    (net (code "253") (name "unconnected-(U2D-TEST_GPIO[44]_3-PadE34)") (class "Default")
      (node (ref "U2") (pin "E34") (pinfunction "TEST_GPIO[44]_3_E34") (pintype "passive+no_connect"))
    )
    (net (code "254") (name "unconnected-(U2D-TEST_GPIO[45]_3-PadC35)") (class "Default")
      (node (ref "U2") (pin "C35") (pinfunction "TEST_GPIO[45]_3_C35") (pintype "passive+no_connect"))
    )
    (net (code "255") (name "unconnected-(U2D-TEST_GPIO[46]_3-PadC36)") (class "Default")
      (node (ref "U2") (pin "C36") (pinfunction "TEST_GPIO[46]_3_C36") (pintype "passive+no_connect"))
    )
    (net (code "256") (name "unconnected-(U2D-TEST_GPIO[47]_3-PadG33)") (class "Default")
      (node (ref "U2") (pin "G33") (pinfunction "TEST_GPIO[47]_3_G33") (pintype "passive+no_connect"))
    )
    (net (code "257") (name "unconnected-(U2D-TEST_GPIO[48]_3-PadE35)") (class "Default")
      (node (ref "U2") (pin "E35") (pinfunction "TEST_GPIO[48]_3_E35") (pintype "passive+no_connect"))
    )
    (net (code "258") (name "unconnected-(U2D-TEST_GPIO[49]_3-PadD36)") (class "Default")
      (node (ref "U2") (pin "D36") (pinfunction "TEST_GPIO[49]_3_D36") (pintype "passive+no_connect"))
    )
    (net (code "259") (name "unconnected-(U2D-TEST_GPIO[50]_3-PadG34)") (class "Default")
      (node (ref "U2") (pin "G34") (pinfunction "TEST_GPIO[50]_3_G34") (pintype "passive+no_connect"))
    )
    (net (code "260") (name "unconnected-(U2D-TEST_GPIO[51]_3-PadF35)") (class "Default")
      (node (ref "U2") (pin "F35") (pinfunction "TEST_GPIO[51]_3_F35") (pintype "passive+no_connect"))
    )
    (net (code "261") (name "unconnected-(U2D-TEST_GPIO[52]_3-PadN34)") (class "Default")
      (node (ref "U2") (pin "N34") (pinfunction "TEST_GPIO[52]_3_N34") (pintype "passive+no_connect"))
    )
    (net (code "262") (name "unconnected-(U2D-TEST_GPIO[53]_3-PadN35)") (class "Default")
      (node (ref "U2") (pin "N35") (pinfunction "TEST_GPIO[53]_3_N35") (pintype "passive+no_connect"))
    )
    (net (code "263") (name "unconnected-(U2D-TEST_GPIO[54]_3-PadP34)") (class "Default")
      (node (ref "U2") (pin "P34") (pinfunction "TEST_GPIO[54]_3_P34") (pintype "passive+no_connect"))
    )
    (net (code "264") (name "unconnected-(U2D-TEST_GPIO[55]_3-PadP33)") (class "Default")
      (node (ref "U2") (pin "P33") (pinfunction "TEST_GPIO[55]_3_P33") (pintype "passive+no_connect"))
    )
    (net (code "265") (name "unconnected-(U2D-TEST_GPIO[56]_3-PadN36)") (class "Default")
      (node (ref "U2") (pin "N36") (pinfunction "TEST_GPIO[56]_3_N36") (pintype "passive+no_connect"))
    )
    (net (code "266") (name "unconnected-(U2D-TEST_GPIO[57]_3-PadP36)") (class "Default")
      (node (ref "U2") (pin "P36") (pinfunction "TEST_GPIO[57]_3_P36") (pintype "passive+no_connect"))
    )
    (net (code "267") (name "unconnected-(U2D-TEST_GPIO[58]_3-PadR34)") (class "Default")
      (node (ref "U2") (pin "R34") (pinfunction "TEST_GPIO[58]_3_R34") (pintype "passive+no_connect"))
    )
    (net (code "268") (name "unconnected-(U2D-TEST_GPIO[59]_3-PadR33)") (class "Default")
      (node (ref "U2") (pin "R33") (pinfunction "TEST_GPIO[59]_3_R33") (pintype "passive+no_connect"))
    )
    (net (code "269") (name "unconnected-(U2D-TEST_GPIO[60]_3-PadR35)") (class "Default")
      (node (ref "U2") (pin "R35") (pinfunction "TEST_GPIO[60]_3_R35") (pintype "passive+no_connect"))
    )
    (net (code "270") (name "unconnected-(U2D-TEST_GPIO[61]_3-PadT36)") (class "Default")
      (node (ref "U2") (pin "T36") (pinfunction "TEST_GPIO[61]_3_T36") (pintype "passive+no_connect"))
    )
    (net (code "271") (name "unconnected-(U2D-TEST_GPIO[62]_3-PadR36)") (class "Default")
      (node (ref "U2") (pin "R36") (pinfunction "TEST_GPIO[62]_3_R36") (pintype "passive+no_connect"))
    )
    (net (code "272") (name "unconnected-(U2D-TEST_GPIO[63]_3-PadT35)") (class "Default")
      (node (ref "U2") (pin "T35") (pinfunction "TEST_GPIO[63]_3_T35") (pintype "passive+no_connect"))
    )
    (net (code "273") (name "unconnected-(U2D-TEST_GPIO[64]_3-PadT33)") (class "Default")
      (node (ref "U2") (pin "T33") (pinfunction "TEST_GPIO[64]_3_T33") (pintype "passive+no_connect"))
    )
    (net (code "274") (name "unconnected-(U2D-TEST_GPIO[65]_3-PadU34)") (class "Default")
      (node (ref "U2") (pin "U34") (pinfunction "TEST_GPIO[65]_3_U34") (pintype "passive+no_connect"))
    )
    (net (code "275") (name "unconnected-(U2D-TEST_GPIO[66]_3-PadU35)") (class "Default")
      (node (ref "U2") (pin "U35") (pinfunction "TEST_GPIO[66]_3_U35") (pintype "passive+no_connect"))
    )
    (net (code "276") (name "unconnected-(U2D-TEST_GPIO[67]_3-PadU33)") (class "Default")
      (node (ref "U2") (pin "U33") (pinfunction "TEST_GPIO[67]_3_U33") (pintype "passive+no_connect"))
    )
    (net (code "277") (name "unconnected-(U2D-TEST_GPIO[68]_3-PadV36)") (class "Default")
      (node (ref "U2") (pin "V36") (pinfunction "TEST_GPIO[68]_3_V36") (pintype "passive+no_connect"))
    )
    (net (code "278") (name "unconnected-(U2D-TEST_GPIO[69]_3-PadV34)") (class "Default")
      (node (ref "U2") (pin "V34") (pinfunction "TEST_GPIO[69]_3_V34") (pintype "passive+no_connect"))
    )
    (net (code "279") (name "unconnected-(U2D-TEST_GPIO[70]_3-PadV35)") (class "Default")
      (node (ref "U2") (pin "V35") (pinfunction "TEST_GPIO[70]_3_V35") (pintype "passive+no_connect"))
    )
    (net (code "280") (name "unconnected-(U2D-TEST_GPIO[71]_3-PadV32)") (class "Default")
      (node (ref "U2") (pin "V32") (pinfunction "TEST_GPIO[71]_3_V32") (pintype "passive+no_connect"))
    )
    (net (code "281") (name "unconnected-(U2E-DBG_SPARE[0]_4-PadC12)") (class "Default")
      (node (ref "U2") (pin "C12") (pinfunction "DBG_SPARE[0]_4_C12") (pintype "passive+no_connect"))
    )
    (net (code "282") (name "unconnected-(U2E-DBG_SPARE[1]_4-PadB12)") (class "Default")
      (node (ref "U2") (pin "B12") (pinfunction "DBG_SPARE[1]_4_B12") (pintype "passive+no_connect"))
    )
    (net (code "283") (name "unconnected-(U2E-JTG_TCK_4-PadL4)") (class "Default")
      (node (ref "U2") (pin "L4") (pinfunction "JTG_TCK_4_L4") (pintype "passive+no_connect"))
    )
    (net (code "284") (name "unconnected-(U2E-JTG_TDI_4-PadL1)") (class "Default")
      (node (ref "U2") (pin "L1") (pinfunction "JTG_TDI_4_L1") (pintype "passive+no_connect"))
    )
    (net (code "285") (name "unconnected-(U2E-JTG_TDO_4-PadM3)") (class "Default")
      (node (ref "U2") (pin "M3") (pinfunction "JTG_TDO_4_M3") (pintype "passive+no_connect"))
    )
    (net (code "286") (name "unconnected-(U2E-JTG_TMS_4-PadM1)") (class "Default")
      (node (ref "U2") (pin "M1") (pinfunction "JTG_TMS_4_M1") (pintype "passive+no_connect"))
    )
    (net (code "287") (name "unconnected-(U2E-TEST_GPIO[0]_4-PadV2)") (class "Default")
      (node (ref "U2") (pin "V2") (pinfunction "TEST_GPIO[0]_4_V2") (pintype "passive+no_connect"))
    )
    (net (code "288") (name "unconnected-(U2E-TEST_GPIO[1]_4-PadU2)") (class "Default")
      (node (ref "U2") (pin "U2") (pinfunction "TEST_GPIO[1]_4_U2") (pintype "passive+no_connect"))
    )
    (net (code "289") (name "unconnected-(U2E-TEST_GPIO[2]_4-PadU3)") (class "Default")
      (node (ref "U2") (pin "U3") (pinfunction "TEST_GPIO[2]_4_U3") (pintype "passive+no_connect"))
    )
    (net (code "290") (name "unconnected-(U2E-TEST_GPIO[3]_4-PadU1)") (class "Default")
      (node (ref "U2") (pin "U1") (pinfunction "TEST_GPIO[3]_4_U1") (pintype "passive+no_connect"))
    )
    (net (code "291") (name "unconnected-(U2E-TEST_GPIO[4]_4-PadT4)") (class "Default")
      (node (ref "U2") (pin "T4") (pinfunction "TEST_GPIO[4]_4_T4") (pintype "passive+no_connect"))
    )
    (net (code "292") (name "unconnected-(U2E-TEST_GPIO[5]_4-PadT1)") (class "Default")
      (node (ref "U2") (pin "T1") (pinfunction "TEST_GPIO[5]_4_T1") (pintype "passive+no_connect"))
    )
    (net (code "293") (name "unconnected-(U2E-TEST_GPIO[6]_4-PadT3)") (class "Default")
      (node (ref "U2") (pin "T3") (pinfunction "TEST_GPIO[6]_4_T3") (pintype "passive+no_connect"))
    )
    (net (code "294") (name "unconnected-(U2E-TEST_GPIO[7]_4-PadR4)") (class "Default")
      (node (ref "U2") (pin "R4") (pinfunction "TEST_GPIO[7]_4_R4") (pintype "passive+no_connect"))
    )
    (net (code "295") (name "unconnected-(U2E-TEST_GPIO[8]_4-PadR3)") (class "Default")
      (node (ref "U2") (pin "R3") (pinfunction "TEST_GPIO[8]_4_R3") (pintype "passive+no_connect"))
    )
    (net (code "296") (name "unconnected-(U2E-TEST_GPIO[9]_4-PadR1)") (class "Default")
      (node (ref "U2") (pin "R1") (pinfunction "TEST_GPIO[9]_4_R1") (pintype "passive+no_connect"))
    )
    (net (code "297") (name "unconnected-(U2E-TEST_GPIO[10]_4-PadR2)") (class "Default")
      (node (ref "U2") (pin "R2") (pinfunction "TEST_GPIO[10]_4_R2") (pintype "passive+no_connect"))
    )
    (net (code "298") (name "unconnected-(U2E-TEST_GPIO[11]_4-PadP4)") (class "Default")
      (node (ref "U2") (pin "P4") (pinfunction "TEST_GPIO[11]_4_P4") (pintype "passive+no_connect"))
    )
    (net (code "299") (name "unconnected-(U2E-TEST_GPIO[12]_4-PadP2)") (class "Default")
      (node (ref "U2") (pin "P2") (pinfunction "TEST_GPIO[12]_4_P2") (pintype "passive+no_connect"))
    )
    (net (code "300") (name "unconnected-(U2E-TEST_GPIO[13]_4-PadN2)") (class "Default")
      (node (ref "U2") (pin "N2") (pinfunction "TEST_GPIO[13]_4_N2") (pintype "passive+no_connect"))
    )
    (net (code "301") (name "unconnected-(U2E-TEST_GPIO[14]_4-PadP1)") (class "Default")
      (node (ref "U2") (pin "P1") (pinfunction "TEST_GPIO[14]_4_P1") (pintype "passive+no_connect"))
    )
    (net (code "302") (name "unconnected-(U2E-TEST_GPIO[15]_4-PadN3)") (class "Default")
      (node (ref "U2") (pin "N3") (pinfunction "TEST_GPIO[15]_4_N3") (pintype "passive+no_connect"))
    )
    (net (code "303") (name "unconnected-(U2E-TEST_GPIO[16]_4-PadL3)") (class "Default")
      (node (ref "U2") (pin "L3") (pinfunction "TEST_GPIO[16]_4_L3") (pintype "passive+no_connect"))
    )
    (net (code "304") (name "unconnected-(U2E-TEST_GPIO[17]_4-PadK1)") (class "Default")
      (node (ref "U2") (pin "K1") (pinfunction "TEST_GPIO[17]_4_K1") (pintype "passive+no_connect"))
    )
    (net (code "305") (name "unconnected-(U2E-TEST_GPIO[18]_4-PadK2)") (class "Default")
      (node (ref "U2") (pin "K2") (pinfunction "TEST_GPIO[18]_4_K2") (pintype "passive+no_connect"))
    )
    (net (code "306") (name "unconnected-(U2E-TEST_GPIO[19]_4-PadK4)") (class "Default")
      (node (ref "U2") (pin "K4") (pinfunction "TEST_GPIO[19]_4_K4") (pintype "passive+no_connect"))
    )
    (net (code "307") (name "unconnected-(U2E-TEST_GPIO[20]_4-PadK3)") (class "Default")
      (node (ref "U2") (pin "K3") (pinfunction "TEST_GPIO[20]_4_K3") (pintype "passive+no_connect"))
    )
    (net (code "308") (name "unconnected-(U2E-TEST_GPIO[21]_4-PadJ1)") (class "Default")
      (node (ref "U2") (pin "J1") (pinfunction "TEST_GPIO[21]_4_J1") (pintype "passive+no_connect"))
    )
    (net (code "309") (name "unconnected-(U2E-TEST_GPIO[22]_4-PadJ2)") (class "Default")
      (node (ref "U2") (pin "J2") (pinfunction "TEST_GPIO[22]_4_J2") (pintype "passive+no_connect"))
    )
    (net (code "310") (name "unconnected-(U2E-TEST_GPIO[23]_4-PadH2)") (class "Default")
      (node (ref "U2") (pin "H2") (pinfunction "TEST_GPIO[23]_4_H2") (pintype "passive+no_connect"))
    )
    (net (code "311") (name "unconnected-(U2E-TEST_GPIO[24]_4-PadJ4)") (class "Default")
      (node (ref "U2") (pin "J4") (pinfunction "TEST_GPIO[24]_4_J4") (pintype "passive+no_connect"))
    )
    (net (code "312") (name "unconnected-(U2E-TEST_GPIO[25]_4-PadH3)") (class "Default")
      (node (ref "U2") (pin "H3") (pinfunction "TEST_GPIO[25]_4_H3") (pintype "passive+no_connect"))
    )
    (net (code "313") (name "unconnected-(U2E-TEST_GPIO[26]_4-PadH4)") (class "Default")
      (node (ref "U2") (pin "H4") (pinfunction "TEST_GPIO[26]_4_H4") (pintype "passive+no_connect"))
    )
    (net (code "314") (name "unconnected-(U2E-TEST_GPIO[27]_4-PadG2)") (class "Default")
      (node (ref "U2") (pin "G2") (pinfunction "TEST_GPIO[27]_4_G2") (pintype "passive+no_connect"))
    )
    (net (code "315") (name "unconnected-(U2E-TEST_GPIO[28]_4-PadG1)") (class "Default")
      (node (ref "U2") (pin "G1") (pinfunction "TEST_GPIO[28]_4_G1") (pintype "passive+no_connect"))
    )
    (net (code "316") (name "unconnected-(U2E-TEST_GPIO[29]_4-PadG3)") (class "Default")
      (node (ref "U2") (pin "G3") (pinfunction "TEST_GPIO[29]_4_G3") (pintype "passive+no_connect"))
    )
    (net (code "317") (name "unconnected-(U2E-TEST_GPIO[30]_4-PadF1)") (class "Default")
      (node (ref "U2") (pin "F1") (pinfunction "TEST_GPIO[30]_4_F1") (pintype "passive+no_connect"))
    )
    (net (code "318") (name "unconnected-(U2E-TEST_GPIO[31]_4-PadE1)") (class "Default")
      (node (ref "U2") (pin "E1") (pinfunction "TEST_GPIO[31]_4_E1") (pintype "passive+no_connect"))
    )
    (net (code "319") (name "unconnected-(U2E-TEST_GPIO[32]_4-PadF3)") (class "Default")
      (node (ref "U2") (pin "F3") (pinfunction "TEST_GPIO[32]_4_F3") (pintype "passive+no_connect"))
    )
    (net (code "320") (name "unconnected-(U2E-TEST_GPIO[33]_4-PadF4)") (class "Default")
      (node (ref "U2") (pin "F4") (pinfunction "TEST_GPIO[33]_4_F4") (pintype "passive+no_connect"))
    )
    (net (code "321") (name "unconnected-(U2E-TEST_GPIO[34]_4-PadE4)") (class "Default")
      (node (ref "U2") (pin "E4") (pinfunction "TEST_GPIO[34]_4_E4") (pintype "passive+no_connect"))
    )
    (net (code "322") (name "unconnected-(U2E-TEST_GPIO[35]_4-PadD1)") (class "Default")
      (node (ref "U2") (pin "D1") (pinfunction "TEST_GPIO[35]_4_D1") (pintype "passive+no_connect"))
    )
    (net (code "323") (name "unconnected-(U2E-TEST_GPIO[36]_4-PadD2)") (class "Default")
      (node (ref "U2") (pin "D2") (pinfunction "TEST_GPIO[36]_4_D2") (pintype "passive+no_connect"))
    )
    (net (code "324") (name "unconnected-(U2E-TEST_GPIO[37]_4-PadD4)") (class "Default")
      (node (ref "U2") (pin "D4") (pinfunction "TEST_GPIO[37]_4_D4") (pintype "passive+no_connect"))
    )
    (net (code "325") (name "unconnected-(U2E-TEST_GPIO[38]_4-PadC2)") (class "Default")
      (node (ref "U2") (pin "C2") (pinfunction "TEST_GPIO[38]_4_C2") (pintype "passive+no_connect"))
    )
    (net (code "326") (name "unconnected-(U2E-TEST_GPIO[39]_4-PadD5)") (class "Default")
      (node (ref "U2") (pin "D5") (pinfunction "TEST_GPIO[39]_4_D5") (pintype "passive+no_connect"))
    )
    (net (code "327") (name "unconnected-(U2E-TEST_GPIO[40]_4-PadC3)") (class "Default")
      (node (ref "U2") (pin "C3") (pinfunction "TEST_GPIO[40]_4_C3") (pintype "passive+no_connect"))
    )
    (net (code "328") (name "unconnected-(U2E-TEST_GPIO[41]_4-PadC4)") (class "Default")
      (node (ref "U2") (pin "C4") (pinfunction "TEST_GPIO[41]_4_C4") (pintype "passive+no_connect"))
    )
    (net (code "329") (name "unconnected-(U2E-TEST_GPIO[42]_4-PadB2)") (class "Default")
      (node (ref "U2") (pin "B2") (pinfunction "TEST_GPIO[42]_4_B2") (pintype "passive+no_connect"))
    )
    (net (code "330") (name "unconnected-(U2E-TEST_GPIO[43]_4-PadD6)") (class "Default")
      (node (ref "U2") (pin "D6") (pinfunction "TEST_GPIO[43]_4_D6") (pintype "passive+no_connect"))
    )
    (net (code "331") (name "unconnected-(U2E-TEST_GPIO[44]_4-PadC5)") (class "Default")
      (node (ref "U2") (pin "C5") (pinfunction "TEST_GPIO[44]_4_C5") (pintype "passive+no_connect"))
    )
    (net (code "332") (name "unconnected-(U2E-TEST_GPIO[45]_4-PadB3)") (class "Default")
      (node (ref "U2") (pin "B3") (pinfunction "TEST_GPIO[45]_4_B3") (pintype "passive+no_connect"))
    )
    (net (code "333") (name "unconnected-(U2E-TEST_GPIO[46]_4-PadA3)") (class "Default")
      (node (ref "U2") (pin "A3") (pinfunction "TEST_GPIO[46]_4_A3") (pintype "passive+no_connect"))
    )
    (net (code "334") (name "unconnected-(U2E-TEST_GPIO[47]_4-PadD7)") (class "Default")
      (node (ref "U2") (pin "D7") (pinfunction "TEST_GPIO[47]_4_D7") (pintype "passive+no_connect"))
    )
    (net (code "335") (name "unconnected-(U2E-TEST_GPIO[48]_4-PadB5)") (class "Default")
      (node (ref "U2") (pin "B5") (pinfunction "TEST_GPIO[48]_4_B5") (pintype "passive+no_connect"))
    )
    (net (code "336") (name "unconnected-(U2E-TEST_GPIO[49]_4-PadA4)") (class "Default")
      (node (ref "U2") (pin "A4") (pinfunction "TEST_GPIO[49]_4_A4") (pintype "passive+no_connect"))
    )
    (net (code "337") (name "unconnected-(U2E-TEST_GPIO[50]_4-PadC7)") (class "Default")
      (node (ref "U2") (pin "C7") (pinfunction "TEST_GPIO[50]_4_C7") (pintype "passive+no_connect"))
    )
    (net (code "338") (name "unconnected-(U2E-TEST_GPIO[51]_4-PadB6)") (class "Default")
      (node (ref "U2") (pin "B6") (pinfunction "TEST_GPIO[51]_4_B6") (pintype "passive+no_connect"))
    )
    (net (code "339") (name "unconnected-(U2E-TEST_GPIO[52]_4-PadC13)") (class "Default")
      (node (ref "U2") (pin "C13") (pinfunction "TEST_GPIO[52]_4_C13") (pintype "passive+no_connect"))
    )
    (net (code "340") (name "unconnected-(U2E-TEST_GPIO[53]_4-PadB13)") (class "Default")
      (node (ref "U2") (pin "B13") (pinfunction "TEST_GPIO[53]_4_B13") (pintype "passive+no_connect"))
    )
    (net (code "341") (name "unconnected-(U2E-TEST_GPIO[54]_4-PadC14)") (class "Default")
      (node (ref "U2") (pin "C14") (pinfunction "TEST_GPIO[54]_4_C14") (pintype "passive+no_connect"))
    )
    (net (code "342") (name "unconnected-(U2E-TEST_GPIO[55]_4-PadD14)") (class "Default")
      (node (ref "U2") (pin "D14") (pinfunction "TEST_GPIO[55]_4_D14") (pintype "passive+no_connect"))
    )
    (net (code "343") (name "unconnected-(U2E-TEST_GPIO[56]_4-PadA13)") (class "Default")
      (node (ref "U2") (pin "A13") (pinfunction "TEST_GPIO[56]_4_A13") (pintype "passive+no_connect"))
    )
    (net (code "344") (name "unconnected-(U2E-TEST_GPIO[57]_4-PadA14)") (class "Default")
      (node (ref "U2") (pin "A14") (pinfunction "TEST_GPIO[57]_4_A14") (pintype "passive+no_connect"))
    )
    (net (code "345") (name "unconnected-(U2E-TEST_GPIO[58]_4-PadC15)") (class "Default")
      (node (ref "U2") (pin "C15") (pinfunction "TEST_GPIO[58]_4_C15") (pintype "passive+no_connect"))
    )
    (net (code "346") (name "unconnected-(U2E-TEST_GPIO[59]_4-PadD15)") (class "Default")
      (node (ref "U2") (pin "D15") (pinfunction "TEST_GPIO[59]_4_D15") (pintype "passive+no_connect"))
    )
    (net (code "347") (name "unconnected-(U2E-TEST_GPIO[60]_4-PadB15)") (class "Default")
      (node (ref "U2") (pin "B15") (pinfunction "TEST_GPIO[60]_4_B15") (pintype "passive+no_connect"))
    )
    (net (code "348") (name "unconnected-(U2E-TEST_GPIO[61]_4-PadA16)") (class "Default")
      (node (ref "U2") (pin "A16") (pinfunction "TEST_GPIO[61]_4_A16") (pintype "passive+no_connect"))
    )
    (net (code "349") (name "unconnected-(U2E-TEST_GPIO[62]_4-PadA15)") (class "Default")
      (node (ref "U2") (pin "A15") (pinfunction "TEST_GPIO[62]_4_A15") (pintype "passive+no_connect"))
    )
    (net (code "350") (name "unconnected-(U2E-TEST_GPIO[63]_4-PadB16)") (class "Default")
      (node (ref "U2") (pin "B16") (pinfunction "TEST_GPIO[63]_4_B16") (pintype "passive+no_connect"))
    )
    (net (code "351") (name "unconnected-(U2E-TEST_GPIO[64]_4-PadD16)") (class "Default")
      (node (ref "U2") (pin "D16") (pinfunction "TEST_GPIO[64]_4_D16") (pintype "passive+no_connect"))
    )
    (net (code "352") (name "unconnected-(U2E-TEST_GPIO[65]_4-PadC17)") (class "Default")
      (node (ref "U2") (pin "C17") (pinfunction "TEST_GPIO[65]_4_C17") (pintype "passive+no_connect"))
    )
    (net (code "353") (name "unconnected-(U2E-TEST_GPIO[66]_4-PadB17)") (class "Default")
      (node (ref "U2") (pin "B17") (pinfunction "TEST_GPIO[66]_4_B17") (pintype "passive+no_connect"))
    )
    (net (code "354") (name "unconnected-(U2E-TEST_GPIO[67]_4-PadD17)") (class "Default")
      (node (ref "U2") (pin "D17") (pinfunction "TEST_GPIO[67]_4_D17") (pintype "passive+no_connect"))
    )
    (net (code "355") (name "unconnected-(U2E-TEST_GPIO[68]_4-PadA18)") (class "Default")
      (node (ref "U2") (pin "A18") (pinfunction "TEST_GPIO[68]_4_A18") (pintype "passive+no_connect"))
    )
    (net (code "356") (name "unconnected-(U2E-TEST_GPIO[69]_4-PadC18)") (class "Default")
      (node (ref "U2") (pin "C18") (pinfunction "TEST_GPIO[69]_4_C18") (pintype "passive+no_connect"))
    )
    (net (code "357") (name "unconnected-(U2E-TEST_GPIO[70]_4-PadB18)") (class "Default")
      (node (ref "U2") (pin "B18") (pinfunction "TEST_GPIO[70]_4_B18") (pintype "passive+no_connect"))
    )
    (net (code "358") (name "unconnected-(U2E-TEST_GPIO[71]_4-PadE18)") (class "Default")
      (node (ref "U2") (pin "E18") (pinfunction "TEST_GPIO[71]_4_E18") (pintype "passive+no_connect"))
    )
  )
)
